# Cornverter.net
KiCad netlist of a schematic drawn in EAGLE
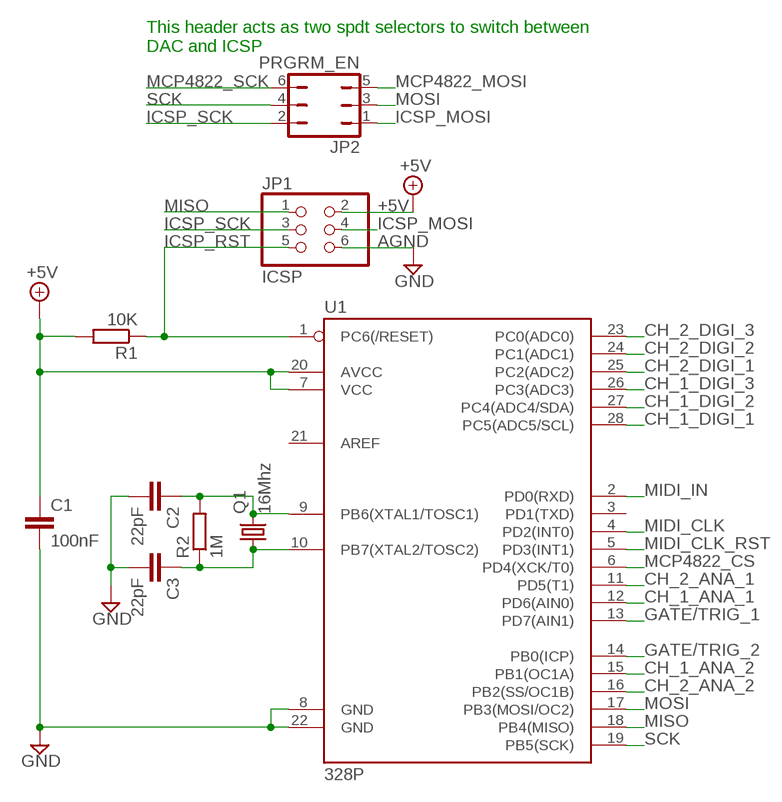
[diagram p0: schematic, sheet 1]
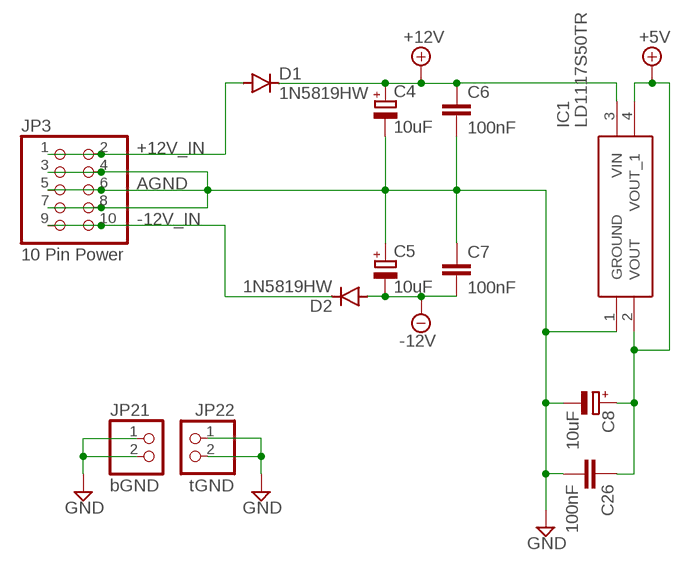
[diagram p1: schematic, sheet 2]
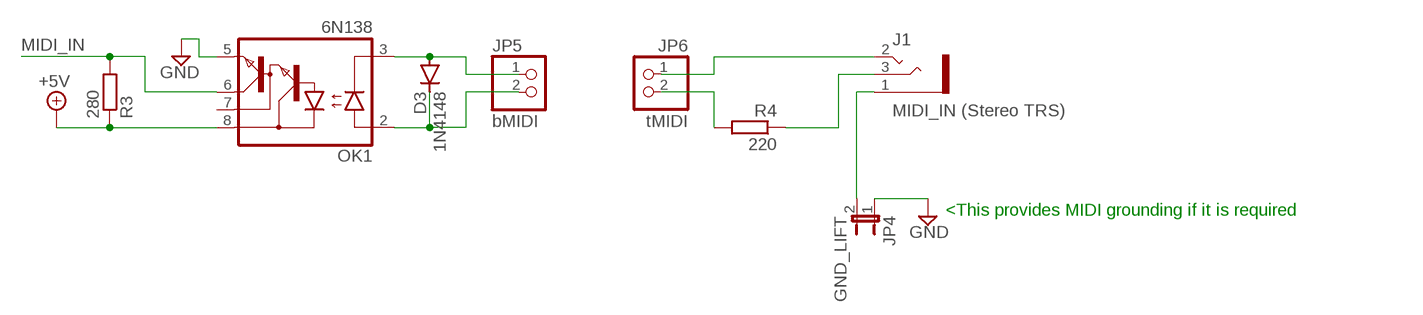
[diagram p2: schematic, sheet 3]
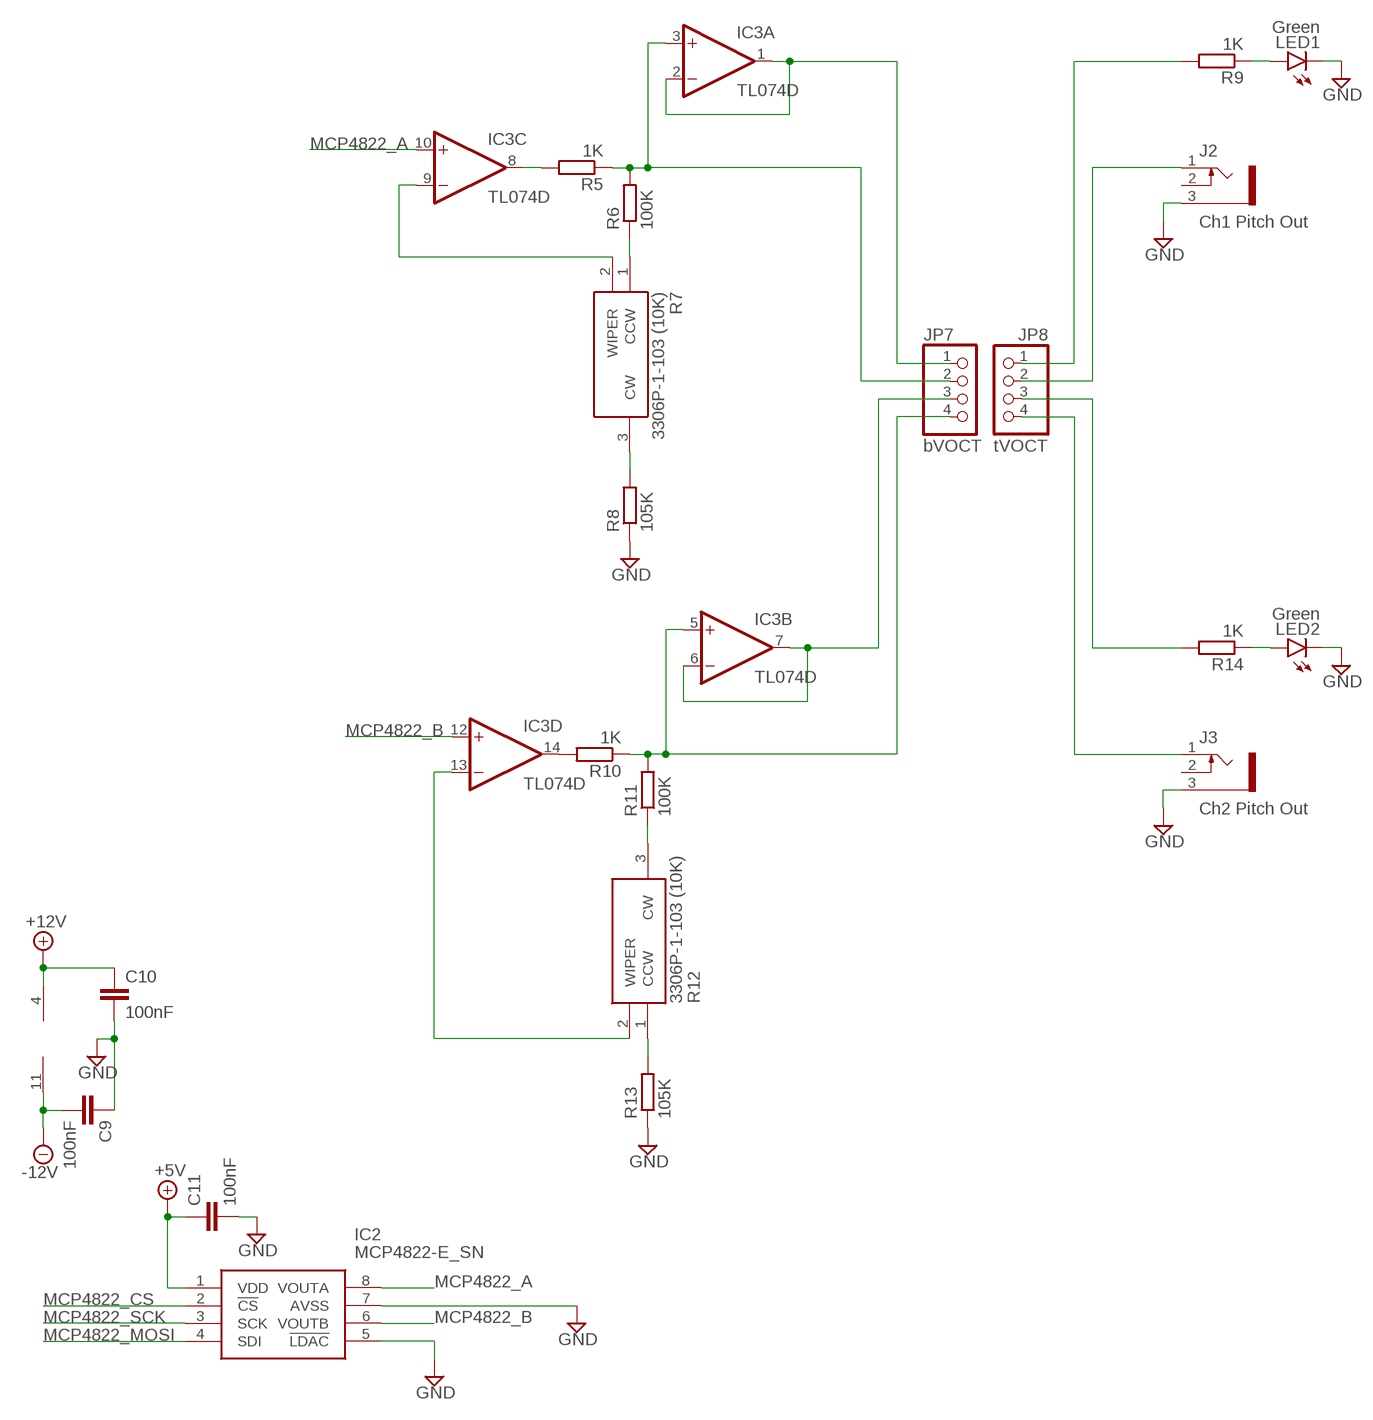
[diagram p3: schematic, sheet 4]
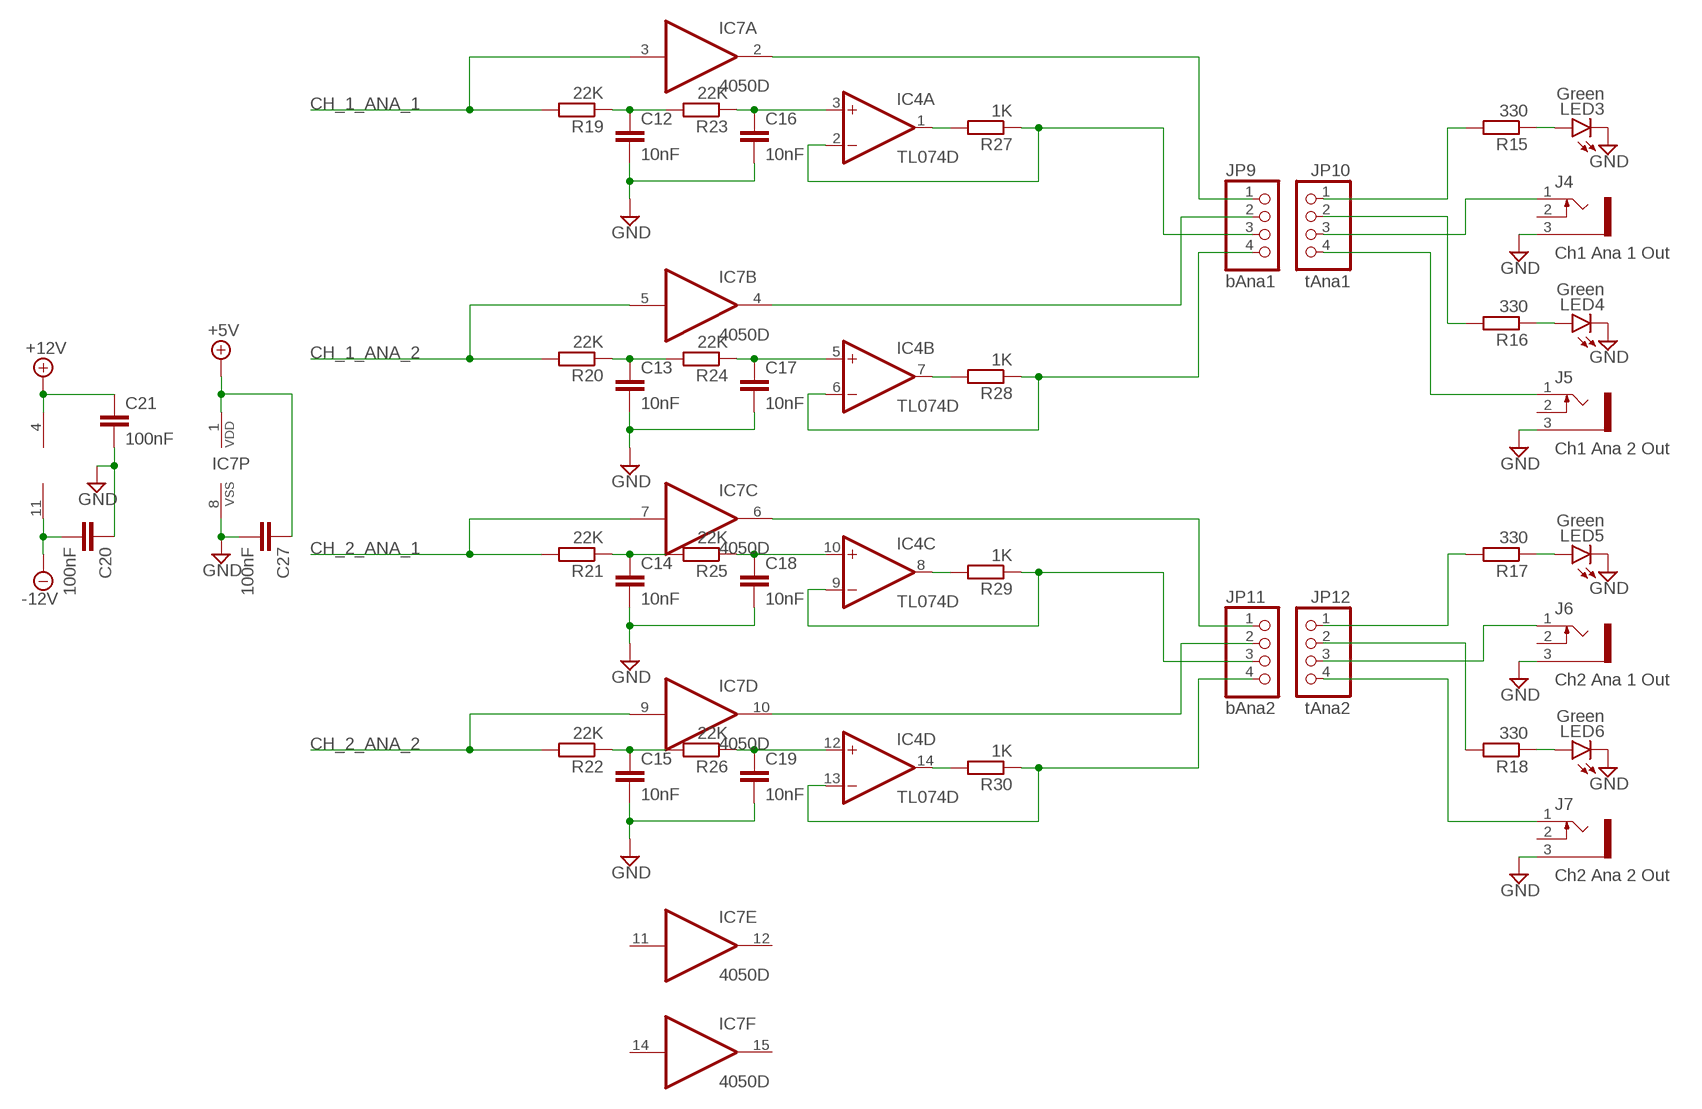
[diagram p4: schematic, sheet 5]
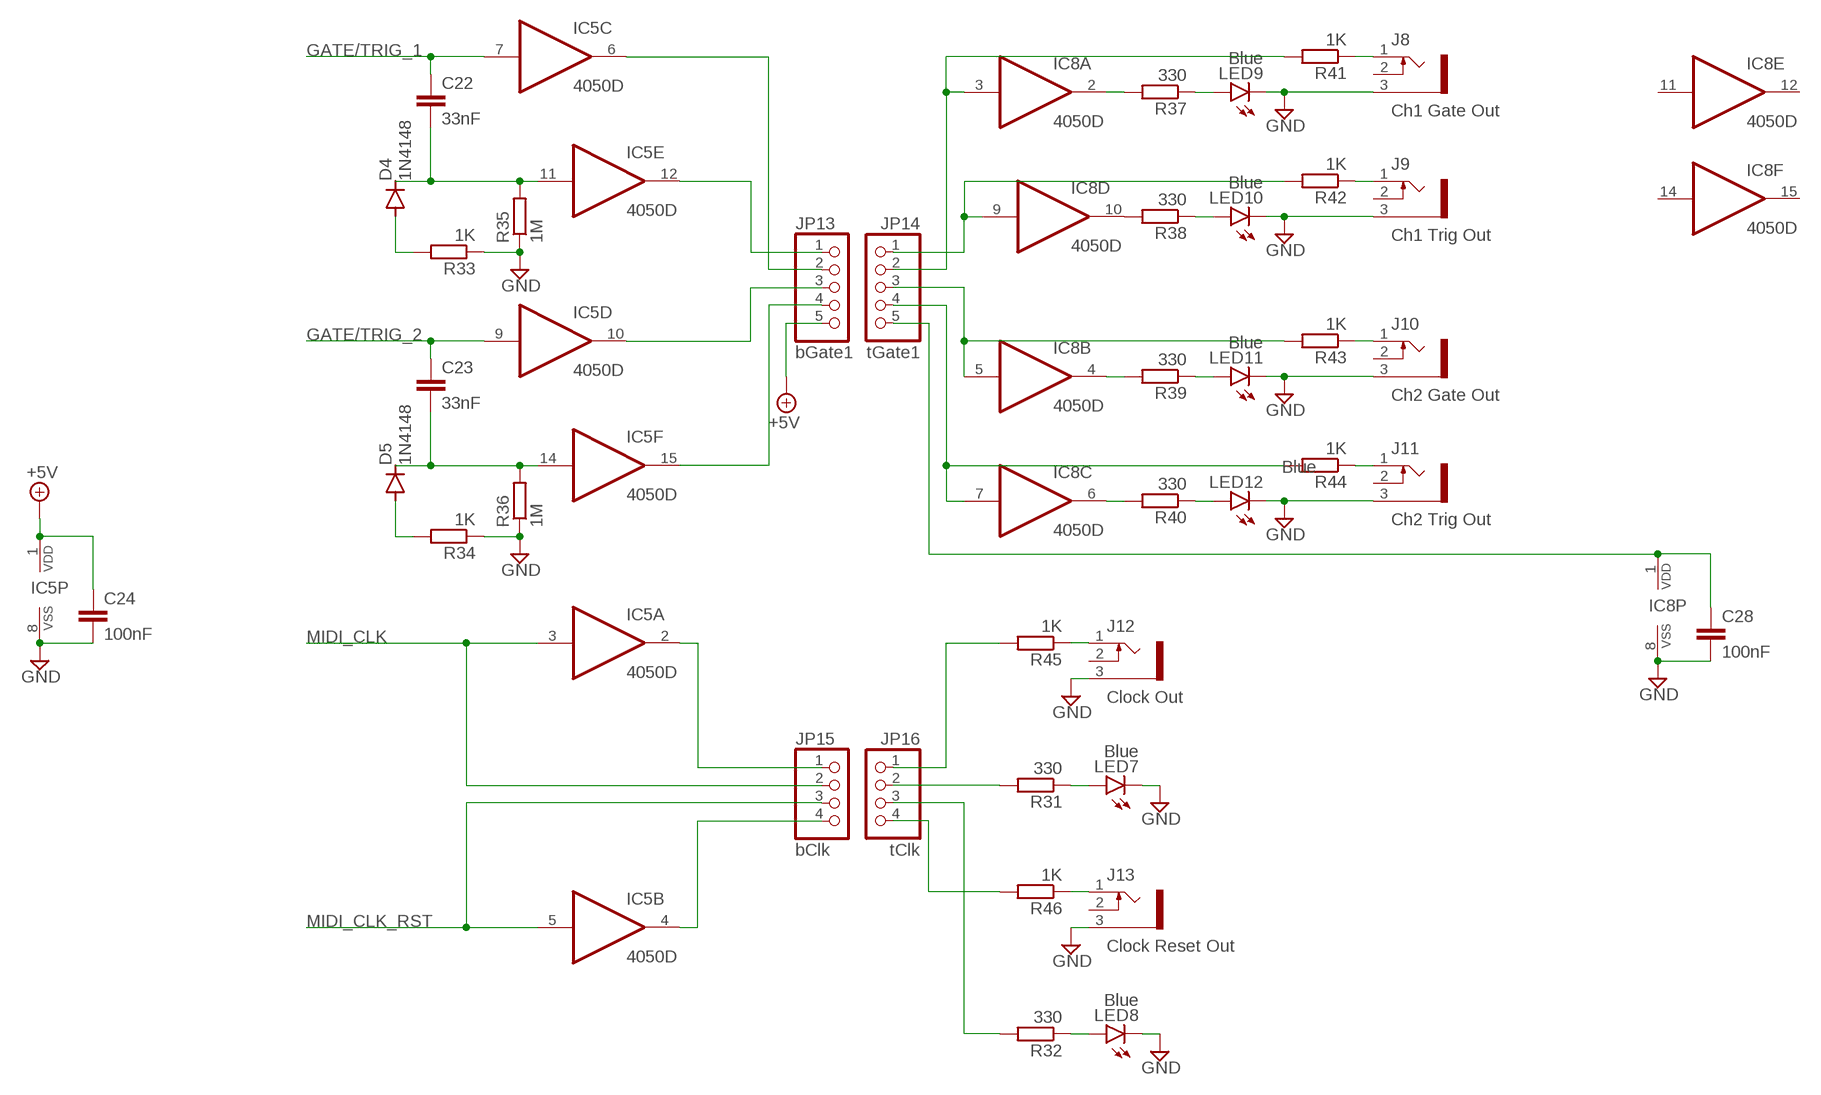
[diagram p5: schematic, sheet 6]
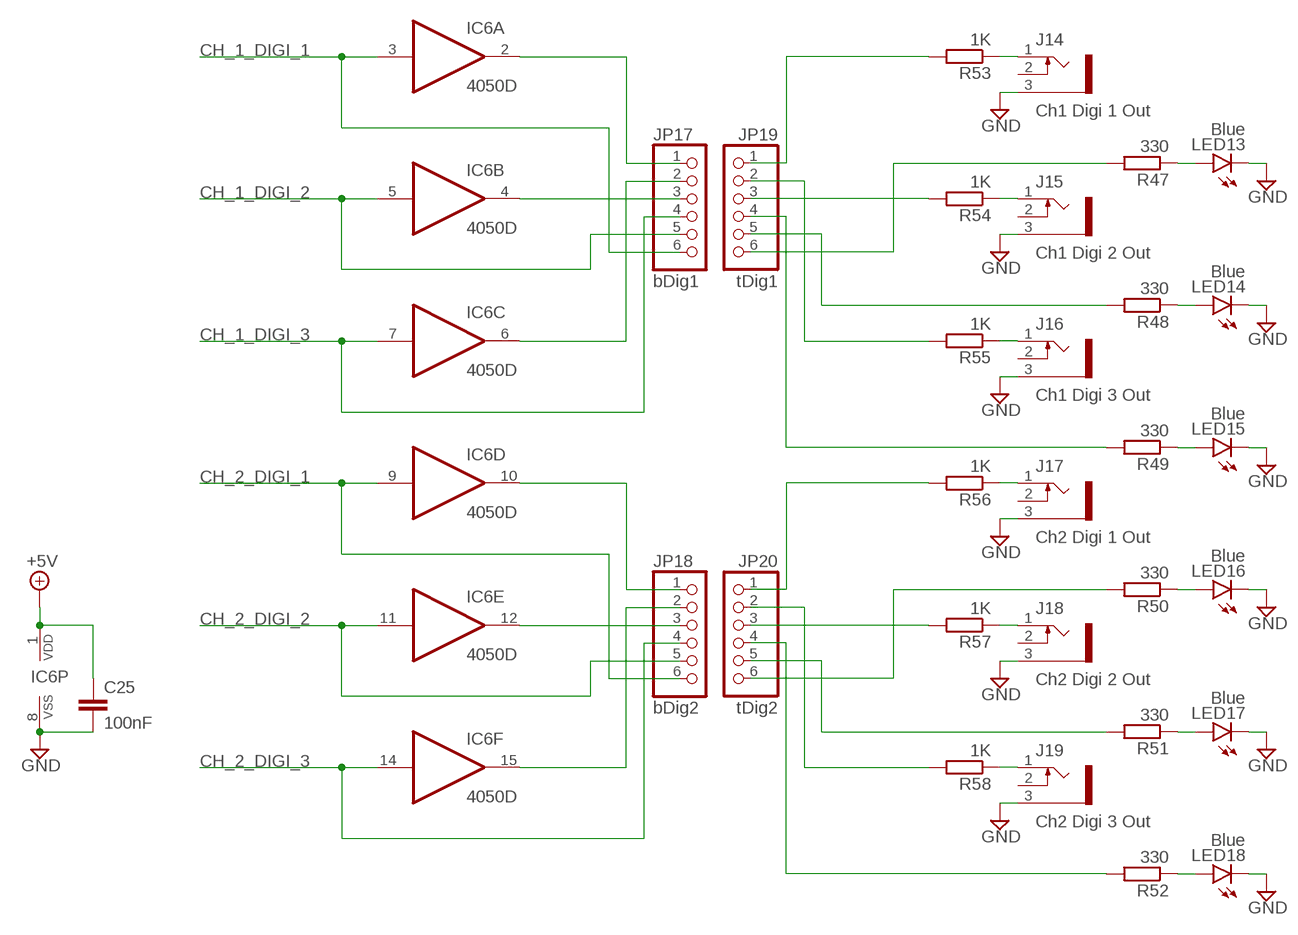
[diagram p6: schematic, sheet 7]

(export (version "E")
  (design (tool "Eeschema 10.0.6"))
  (components
    (comp (ref "C1")
      (value "100nF")
      (footprint "eagle-import:C1206")
      (libsource (lib "eagle-import") (part "C-EUC1206"))
    )
    (comp (ref "C2")
      (value "22pF")
      (footprint "eagle-import:C1206")
      (libsource (lib "eagle-import") (part "C-EUC1206"))
    )
    (comp (ref "C3")
      (value "22pF")
      (footprint "eagle-import:C1206")
      (libsource (lib "eagle-import") (part "C-EUC1206"))
    )
    (comp (ref "JP1")
      (value "ICSP")
      (footprint "eagle-import:2X03")
      (libsource (lib "eagle-import") (part "PINHD-2X3"))
    )
    (comp (ref "JP2")
      (value "PRGRM_EN")
      (footprint "eagle-import:JP3Q")
      (libsource (lib "eagle-import") (part "JP3Q"))
    )
    (comp (ref "Q1")
      (value "16Mhz")
      (footprint "eagle-import:HC49_S")
      (libsource (lib "eagle-import") (part "CRYSTALHC49S"))
    )
    (comp (ref "R1")
      (value "10K")
      (footprint "eagle-import:R1206")
      (libsource (lib "eagle-import") (part "resistor_348_R-EU_R1206"))
    )
    (comp (ref "R2")
      (value "1M")
      (footprint "eagle-import:R1206")
      (libsource (lib "eagle-import") (part "R-EU_R1206"))
    )
    (comp (ref "U1")
      (value "328P")
      (footprint "eagle-import:DIP28")
      (libsource (lib "eagle-import") (part "ATMEGA328P_PDIP"))
    )
    (comp (ref "C22")
      (value "33nF")
      (footprint "eagle-import:C1206")
      (libsource (lib "eagle-import") (part "C-EUC1206"))
    )
    (comp (ref "C23")
      (value "33nF")
      (footprint "eagle-import:C1206")
      (libsource (lib "eagle-import") (part "C-EUC1206"))
    )
    (comp (ref "C24")
      (value "100nF")
      (footprint "eagle-import:C1206")
      (libsource (lib "eagle-import") (part "C-EUC1206"))
    )
    (comp (ref "C28")
      (value "100nF")
      (footprint "eagle-import:C1206")
      (libsource (lib "eagle-import") (part "C-EUC1206"))
    )
    (comp (ref "D4")
      (value "1N4148")
      (footprint "eagle-import:DO35-7")
      (libsource (lib "eagle-import") (part "1N4148DO35-7"))
    )
    (comp (ref "D5")
      (value "1N4148")
      (footprint "eagle-import:DO35-7")
      (libsource (lib "eagle-import") (part "1N4148DO35-7"))
    )
    (comp (ref "IC5")
      (value "4050D")
      (footprint "eagle-import:SO16")
      (libsource (lib "eagle-import") (part "4050D"))
    )
    (comp (ref "IC8")
      (value "4050D")
      (footprint "eagle-import:SO16")
      (libsource (lib "eagle-import") (part "4050D"))
    )
    (comp (ref "J8")
      (value "Ch1 Gate Out")
      (footprint "eagle-import:WQP-PJ301M-12_JACK")
      (libsource (lib "eagle-import") (part "WQP-PJ301M-12_JACK"))
    )
    (comp (ref "J9")
      (value "Ch1 Trig Out")
      (footprint "eagle-import:WQP-PJ301M-12_JACK")
      (libsource (lib "eagle-import") (part "WQP-PJ301M-12_JACK"))
    )
    (comp (ref "J10")
      (value "Ch2 Gate Out")
      (footprint "eagle-import:WQP-PJ301M-12_JACK")
      (libsource (lib "eagle-import") (part "WQP-PJ301M-12_JACK"))
    )
    (comp (ref "J11")
      (value "Ch2 Trig Out")
      (footprint "eagle-import:WQP-PJ301M-12_JACK")
      (libsource (lib "eagle-import") (part "WQP-PJ301M-12_JACK"))
    )
    (comp (ref "J12")
      (value "Clock Out")
      (footprint "eagle-import:WQP-PJ301M-12_JACK")
      (libsource (lib "eagle-import") (part "WQP-PJ301M-12_JACK"))
    )
    (comp (ref "J13")
      (value "Clock Reset Out")
      (footprint "eagle-import:WQP-PJ301M-12_JACK")
      (libsource (lib "eagle-import") (part "WQP-PJ301M-12_JACK"))
    )
    (comp (ref "JP13")
      (value "bGate1")
      (footprint "eagle-import:1X05")
      (libsource (lib "eagle-import") (part "PINHD-1X5"))
    )
    (comp (ref "JP14")
      (value "tGate1")
      (footprint "eagle-import:1X05")
      (libsource (lib "eagle-import") (part "PINHD-1X5"))
    )
    (comp (ref "JP15")
      (value "bClk")
      (footprint "eagle-import:1X04")
      (libsource (lib "eagle-import") (part "PINHD-1X4"))
    )
    (comp (ref "JP16")
      (value "tClk")
      (footprint "eagle-import:1X04")
      (libsource (lib "eagle-import") (part "PINHD-1X4"))
    )
    (comp (ref "LED7")
      (value "Blue")
      (footprint "eagle-import:LED3MM")
      (libsource (lib "eagle-import") (part "LED3MM"))
    )
    (comp (ref "LED8")
      (value "Blue")
      (footprint "eagle-import:LED3MM")
      (libsource (lib "eagle-import") (part "LED3MM"))
    )
    (comp (ref "LED9")
      (value "Blue")
      (footprint "eagle-import:LED3MM")
      (libsource (lib "eagle-import") (part "LED3MM"))
    )
    (comp (ref "LED10")
      (value "Blue")
      (footprint "eagle-import:LED3MM")
      (libsource (lib "eagle-import") (part "LED3MM"))
    )
    (comp (ref "LED11")
      (value "Blue")
      (footprint "eagle-import:LED3MM")
      (libsource (lib "eagle-import") (part "LED3MM"))
    )
    (comp (ref "LED12")
      (value "Blue")
      (footprint "eagle-import:LED3MM")
      (libsource (lib "eagle-import") (part "LED3MM"))
    )
    (comp (ref "R31")
      (value "330")
      (footprint "eagle-import:R1206")
      (libsource (lib "eagle-import") (part "R-EU_R1206"))
    )
    (comp (ref "R32")
      (value "330")
      (footprint "eagle-import:R1206")
      (libsource (lib "eagle-import") (part "R-EU_R1206"))
    )
    (comp (ref "R33")
      (value "1K")
      (footprint "eagle-import:R1206")
      (libsource (lib "eagle-import") (part "R-EU_R1206"))
    )
    (comp (ref "R34")
      (value "1K")
      (footprint "eagle-import:R1206")
      (libsource (lib "eagle-import") (part "R-EU_R1206"))
    )
    (comp (ref "R35")
      (value "1M")
      (footprint "eagle-import:R1206")
      (libsource (lib "eagle-import") (part "R-EU_R1206"))
    )
    (comp (ref "R36")
      (value "1M")
      (footprint "eagle-import:R1206")
      (libsource (lib "eagle-import") (part "R-EU_R1206"))
    )
    (comp (ref "R37")
      (value "330")
      (footprint "eagle-import:R1206")
      (libsource (lib "eagle-import") (part "R-EU_R1206"))
    )
    (comp (ref "R38")
      (value "330")
      (footprint "eagle-import:R1206")
      (libsource (lib "eagle-import") (part "R-EU_R1206"))
    )
    (comp (ref "R39")
      (value "330")
      (footprint "eagle-import:R1206")
      (libsource (lib "eagle-import") (part "R-EU_R1206"))
    )
    (comp (ref "R40")
      (value "330")
      (footprint "eagle-import:R1206")
      (libsource (lib "eagle-import") (part "R-EU_R1206"))
    )
    (comp (ref "R41")
      (value "1K")
      (footprint "eagle-import:R1206")
      (libsource (lib "eagle-import") (part "R-EU_R1206"))
    )
    (comp (ref "R42")
      (value "1K")
      (footprint "eagle-import:R1206")
      (libsource (lib "eagle-import") (part "R-EU_R1206"))
    )
    (comp (ref "R43")
      (value "1K")
      (footprint "eagle-import:R1206")
      (libsource (lib "eagle-import") (part "R-EU_R1206"))
    )
    (comp (ref "R44")
      (value "1K")
      (footprint "eagle-import:R1206")
      (libsource (lib "eagle-import") (part "R-EU_R1206"))
    )
    (comp (ref "R45")
      (value "1K")
      (footprint "eagle-import:R1206")
      (libsource (lib "eagle-import") (part "R-EU_R1206"))
    )
    (comp (ref "R46")
      (value "1K")
      (footprint "eagle-import:R1206")
      (libsource (lib "eagle-import") (part "R-EU_R1206"))
    )
    (comp (ref "C9")
      (value "100nF")
      (footprint "eagle-import:C1206")
      (libsource (lib "eagle-import") (part "C-EUC1206"))
    )
    (comp (ref "C10")
      (value "100nF")
      (footprint "eagle-import:C1206")
      (libsource (lib "eagle-import") (part "C-EUC1206"))
    )
    (comp (ref "C11")
      (value "100nF")
      (footprint "eagle-import:C1206")
      (libsource (lib "eagle-import") (part "C-EUC1206"))
    )
    (comp (ref "IC2")
      (value "MCP4822-E_SN")
      (footprint "eagle-import:SOIC127P600X175-8N")
      (fields
        (field (name "MANUFACTURER_PART_NUMBER") "MCP4822-E/SN")
        (field (name "MOUSER_PART_NUMBER") "579-MCP4822-E/SN")
      )
      (libsource (lib "eagle-import") (part "MCP4822-E_SN"))
    )
    (comp (ref "IC3")
      (value "TL074D")
      (footprint "eagle-import:SO14")
      (libsource (lib "eagle-import") (part "TL074D"))
    )
    (comp (ref "J2")
      (value "Ch1 Pitch Out")
      (footprint "eagle-import:WQP-PJ301M-12_JACK")
      (libsource (lib "eagle-import") (part "WQP-PJ301M-12_JACK"))
    )
    (comp (ref "J3")
      (value "Ch2 Pitch Out")
      (footprint "eagle-import:WQP-PJ301M-12_JACK")
      (libsource (lib "eagle-import") (part "WQP-PJ301M-12_JACK"))
    )
    (comp (ref "JP7")
      (value "bVOCT")
      (footprint "eagle-import:1X04")
      (libsource (lib "eagle-import") (part "PINHD-1X4"))
    )
    (comp (ref "JP8")
      (value "tVOCT")
      (footprint "eagle-import:1X04")
      (libsource (lib "eagle-import") (part "PINHD-1X4"))
    )
    (comp (ref "LED1")
      (value "Green")
      (footprint "eagle-import:LED3MM")
      (libsource (lib "eagle-import") (part "LED3MM"))
    )
    (comp (ref "LED2")
      (value "Green")
      (footprint "eagle-import:LED3MM")
      (libsource (lib "eagle-import") (part "LED3MM"))
    )
    (comp (ref "R5")
      (value "1K")
      (footprint "eagle-import:R1206")
      (libsource (lib "eagle-import") (part "R-EU_R1206"))
    )
    (comp (ref "R6")
      (value "100K")
      (footprint "eagle-import:R1206")
      (libsource (lib "eagle-import") (part "R-EU_R1206"))
    )
    (comp (ref "R7")
      (value "3306P-1-103 (10K)")
      (footprint "eagle-import:3306P1103")
      (fields
        (field (name "MANUFACTURER_PART_NUMBER") "3306P-1-103")
        (field (name "MOUSER_PART_NUMBER") "652-3306P-1-103")
      )
      (libsource (lib "eagle-import") (part "3306P-1-103"))
    )
    (comp (ref "R8")
      (value "105K")
      (footprint "eagle-import:R1206")
      (libsource (lib "eagle-import") (part "R-EU_R1206"))
    )
    (comp (ref "R9")
      (value "1K")
      (footprint "eagle-import:R1206")
      (libsource (lib "eagle-import") (part "R-EU_R1206"))
    )
    (comp (ref "R10")
      (value "1K")
      (footprint "eagle-import:R1206")
      (libsource (lib "eagle-import") (part "R-EU_R1206"))
    )
    (comp (ref "R11")
      (value "100K")
      (footprint "eagle-import:R1206")
      (libsource (lib "eagle-import") (part "R-EU_R1206"))
    )
    (comp (ref "R12")
      (value "3306P-1-103 (10K)")
      (footprint "eagle-import:3306P1103")
      (fields
        (field (name "MANUFACTURER_PART_NUMBER") "3306P-1-103")
        (field (name "MOUSER_PART_NUMBER") "652-3306P-1-103")
      )
      (libsource (lib "eagle-import") (part "3306P-1-103"))
    )
    (comp (ref "R13")
      (value "105K")
      (footprint "eagle-import:R1206")
      (libsource (lib "eagle-import") (part "R-EU_R1206"))
    )
    (comp (ref "R14")
      (value "1K")
      (footprint "eagle-import:R1206")
      (libsource (lib "eagle-import") (part "R-EU_R1206"))
    )
    (comp (ref "C25")
      (value "100nF")
      (footprint "eagle-import:C1206")
      (libsource (lib "eagle-import") (part "C-EUC1206"))
    )
    (comp (ref "IC6")
      (value "4050D")
      (footprint "eagle-import:SO16")
      (libsource (lib "eagle-import") (part "4050D"))
    )
    (comp (ref "J14")
      (value "Ch1 Digi 1 Out")
      (footprint "eagle-import:WQP-PJ301M-12_JACK")
      (libsource (lib "eagle-import") (part "WQP-PJ301M-12_JACK"))
    )
    (comp (ref "J15")
      (value "Ch1 Digi 2 Out")
      (footprint "eagle-import:WQP-PJ301M-12_JACK")
      (libsource (lib "eagle-import") (part "WQP-PJ301M-12_JACK"))
    )
    (comp (ref "J16")
      (value "Ch1 Digi 3 Out")
      (footprint "eagle-import:WQP-PJ301M-12_JACK")
      (libsource (lib "eagle-import") (part "WQP-PJ301M-12_JACK"))
    )
    (comp (ref "J17")
      (value "Ch2 Digi 1 Out")
      (footprint "eagle-import:WQP-PJ301M-12_JACK")
      (libsource (lib "eagle-import") (part "WQP-PJ301M-12_JACK"))
    )
    (comp (ref "J18")
      (value "Ch2 Digi 2 Out")
      (footprint "eagle-import:WQP-PJ301M-12_JACK")
      (libsource (lib "eagle-import") (part "WQP-PJ301M-12_JACK"))
    )
    (comp (ref "J19")
      (value "Ch2 Digi 3 Out")
      (footprint "eagle-import:WQP-PJ301M-12_JACK")
      (libsource (lib "eagle-import") (part "WQP-PJ301M-12_JACK"))
    )
    (comp (ref "JP17")
      (value "bDig1")
      (footprint "eagle-import:1X06")
      (libsource (lib "eagle-import") (part "PINHD-1X6"))
    )
    (comp (ref "JP18")
      (value "bDig2")
      (footprint "eagle-import:1X06")
      (libsource (lib "eagle-import") (part "PINHD-1X6"))
    )
    (comp (ref "JP19")
      (value "tDig1")
      (footprint "eagle-import:1X06")
      (libsource (lib "eagle-import") (part "PINHD-1X6"))
    )
    (comp (ref "JP20")
      (value "tDig2")
      (footprint "eagle-import:1X06")
      (libsource (lib "eagle-import") (part "PINHD-1X6"))
    )
    (comp (ref "LED13")
      (value "Blue")
      (footprint "eagle-import:LED3MM")
      (libsource (lib "eagle-import") (part "LED3MM"))
    )
    (comp (ref "LED14")
      (value "Blue")
      (footprint "eagle-import:LED3MM")
      (libsource (lib "eagle-import") (part "LED3MM"))
    )
    (comp (ref "LED15")
      (value "Blue")
      (footprint "eagle-import:LED3MM")
      (libsource (lib "eagle-import") (part "LED3MM"))
    )
    (comp (ref "LED16")
      (value "Blue")
      (footprint "eagle-import:LED3MM")
      (libsource (lib "eagle-import") (part "LED3MM"))
    )
    (comp (ref "LED17")
      (value "Blue")
      (footprint "eagle-import:LED3MM")
      (libsource (lib "eagle-import") (part "LED3MM"))
    )
    (comp (ref "LED18")
      (value "Blue")
      (footprint "eagle-import:LED3MM")
      (libsource (lib "eagle-import") (part "LED3MM"))
    )
    (comp (ref "R47")
      (value "330")
      (footprint "eagle-import:R1206")
      (libsource (lib "eagle-import") (part "R-EU_R1206"))
    )
    (comp (ref "R48")
      (value "330")
      (footprint "eagle-import:R1206")
      (libsource (lib "eagle-import") (part "R-EU_R1206"))
    )
    (comp (ref "R49")
      (value "330")
      (footprint "eagle-import:R1206")
      (libsource (lib "eagle-import") (part "R-EU_R1206"))
    )
    (comp (ref "R50")
      (value "330")
      (footprint "eagle-import:R1206")
      (libsource (lib "eagle-import") (part "R-EU_R1206"))
    )
    (comp (ref "R51")
      (value "330")
      (footprint "eagle-import:R1206")
      (libsource (lib "eagle-import") (part "R-EU_R1206"))
    )
    (comp (ref "R52")
      (value "330")
      (footprint "eagle-import:R1206")
      (libsource (lib "eagle-import") (part "R-EU_R1206"))
    )
    (comp (ref "R53")
      (value "1K")
      (footprint "eagle-import:R1206")
      (libsource (lib "eagle-import") (part "R-EU_R1206"))
    )
    (comp (ref "R54")
      (value "1K")
      (footprint "eagle-import:R1206")
      (libsource (lib "eagle-import") (part "R-EU_R1206"))
    )
    (comp (ref "R55")
      (value "1K")
      (footprint "eagle-import:R1206")
      (libsource (lib "eagle-import") (part "R-EU_R1206"))
    )
    (comp (ref "R56")
      (value "1K")
      (footprint "eagle-import:R1206")
      (libsource (lib "eagle-import") (part "R-EU_R1206"))
    )
    (comp (ref "R57")
      (value "1K")
      (footprint "eagle-import:R1206")
      (libsource (lib "eagle-import") (part "R-EU_R1206"))
    )
    (comp (ref "R58")
      (value "1K")
      (footprint "eagle-import:R1206")
      (libsource (lib "eagle-import") (part "R-EU_R1206"))
    )
    (comp (ref "D3")
      (value "1N4148")
      (footprint "eagle-import:DO35-7")
      (libsource (lib "eagle-import") (part "1N4148DO35-7"))
    )
    (comp (ref "J1")
      (value "MIDI_IN (Stereo TRS)")
      (footprint "eagle-import:WQP-PJ301M-12-ST_JACK")
      (libsource (lib "eagle-import") (part "WQP-PJ301M-12-ST_JACK"))
    )
    (comp (ref "JP4")
      (value "GND_LIFT")
      (footprint "eagle-import:JP1")
      (libsource (lib "eagle-import") (part "JP1E"))
    )
    (comp (ref "JP5")
      (value "bMIDI")
      (footprint "eagle-import:1X02")
      (libsource (lib "eagle-import") (part "PINHD-1X2"))
    )
    (comp (ref "JP6")
      (value "tMIDI")
      (footprint "eagle-import:1X02")
      (libsource (lib "eagle-import") (part "PINHD-1X2"))
    )
    (comp (ref "OK1")
      (value "6N138")
      (footprint "eagle-import:DIL08")
      (fields (field (name "MF") "VISHAY/TELEFUNKEN") (field (name "SPICEPREFIX") "X"))
      (libsource (lib "eagle-import") (part "6N138"))
    )
    (comp (ref "R3")
      (value "280")
      (footprint "eagle-import:R1206")
      (libsource (lib "eagle-import") (part "R-EU_R1206"))
    )
    (comp (ref "R4")
      (value "220")
      (footprint "eagle-import:R1206")
      (libsource (lib "eagle-import") (part "R-EU_R1206"))
    )
    (comp (ref "C12")
      (value "10nF")
      (footprint "eagle-import:C1206")
      (libsource (lib "eagle-import") (part "C-EUC1206"))
    )
    (comp (ref "C13")
      (value "10nF")
      (footprint "eagle-import:C1206")
      (libsource (lib "eagle-import") (part "C-EUC1206"))
    )
    (comp (ref "C14")
      (value "10nF")
      (footprint "eagle-import:C1206")
      (libsource (lib "eagle-import") (part "C-EUC1206"))
    )
    (comp (ref "C15")
      (value "10nF")
      (footprint "eagle-import:C1206")
      (libsource (lib "eagle-import") (part "C-EUC1206"))
    )
    (comp (ref "C16")
      (value "10nF")
      (footprint "eagle-import:C1206")
      (libsource (lib "eagle-import") (part "C-EUC1206"))
    )
    (comp (ref "C17")
      (value "10nF")
      (footprint "eagle-import:C1206")
      (libsource (lib "eagle-import") (part "C-EUC1206"))
    )
    (comp (ref "C18")
      (value "10nF")
      (footprint "eagle-import:C1206")
      (libsource (lib "eagle-import") (part "C-EUC1206"))
    )
    (comp (ref "C19")
      (value "10nF")
      (footprint "eagle-import:C1206")
      (libsource (lib "eagle-import") (part "C-EUC1206"))
    )
    (comp (ref "C20")
      (value "100nF")
      (footprint "eagle-import:C1206")
      (libsource (lib "eagle-import") (part "C-EUC1206"))
    )
    (comp (ref "C21")
      (value "100nF")
      (footprint "eagle-import:C1206")
      (libsource (lib "eagle-import") (part "C-EUC1206"))
    )
    (comp (ref "C27")
      (value "100nF")
      (footprint "eagle-import:C1206")
      (libsource (lib "eagle-import") (part "C-EUC1206"))
    )
    (comp (ref "IC4")
      (value "TL074D")
      (footprint "eagle-import:SO14")
      (libsource (lib "eagle-import") (part "TL074D"))
    )
    (comp (ref "IC7")
      (value "4050D")
      (footprint "eagle-import:SO16")
      (libsource (lib "eagle-import") (part "4050D"))
    )
    (comp (ref "J4")
      (value "Ch1 Ana 1 Out")
      (footprint "eagle-import:WQP-PJ301M-12_JACK")
      (libsource (lib "eagle-import") (part "WQP-PJ301M-12_JACK"))
    )
    (comp (ref "J5")
      (value "Ch1 Ana 2 Out")
      (footprint "eagle-import:WQP-PJ301M-12_JACK")
      (libsource (lib "eagle-import") (part "WQP-PJ301M-12_JACK"))
    )
    (comp (ref "J6")
      (value "Ch2 Ana 1 Out")
      (footprint "eagle-import:WQP-PJ301M-12_JACK")
      (libsource (lib "eagle-import") (part "WQP-PJ301M-12_JACK"))
    )
    (comp (ref "J7")
      (value "Ch2 Ana 2 Out")
      (footprint "eagle-import:WQP-PJ301M-12_JACK")
      (libsource (lib "eagle-import") (part "WQP-PJ301M-12_JACK"))
    )
    (comp (ref "JP9")
      (value "bAna1")
      (footprint "eagle-import:1X04")
      (libsource (lib "eagle-import") (part "PINHD-1X4"))
    )
    (comp (ref "JP10")
      (value "tAna1")
      (footprint "eagle-import:1X04")
      (libsource (lib "eagle-import") (part "PINHD-1X4"))
    )
    (comp (ref "JP11")
      (value "bAna2")
      (footprint "eagle-import:1X04")
      (libsource (lib "eagle-import") (part "PINHD-1X4"))
    )
    (comp (ref "JP12")
      (value "tAna2")
      (footprint "eagle-import:1X04")
      (libsource (lib "eagle-import") (part "PINHD-1X4"))
    )
    (comp (ref "LED3")
      (value "Green")
      (footprint "eagle-import:LED3MM")
      (libsource (lib "eagle-import") (part "LED3MM"))
    )
    (comp (ref "LED4")
      (value "Green")
      (footprint "eagle-import:LED3MM")
      (libsource (lib "eagle-import") (part "LED3MM"))
    )
    (comp (ref "LED5")
      (value "Green")
      (footprint "eagle-import:LED3MM")
      (libsource (lib "eagle-import") (part "LED3MM"))
    )
    (comp (ref "LED6")
      (value "Green")
      (footprint "eagle-import:LED3MM")
      (libsource (lib "eagle-import") (part "LED3MM"))
    )
    (comp (ref "R15")
      (value "330")
      (footprint "eagle-import:R1206")
      (libsource (lib "eagle-import") (part "R-EU_R1206"))
    )
    (comp (ref "R16")
      (value "330")
      (footprint "eagle-import:R1206")
      (libsource (lib "eagle-import") (part "R-EU_R1206"))
    )
    (comp (ref "R17")
      (value "330")
      (footprint "eagle-import:R1206")
      (libsource (lib "eagle-import") (part "R-EU_R1206"))
    )
    (comp (ref "R18")
      (value "330")
      (footprint "eagle-import:R1206")
      (libsource (lib "eagle-import") (part "R-EU_R1206"))
    )
    (comp (ref "R19")
      (value "22K")
      (footprint "eagle-import:R1206")
      (libsource (lib "eagle-import") (part "R-EU_R1206"))
    )
    (comp (ref "R20")
      (value "22K")
      (footprint "eagle-import:R1206")
      (libsource (lib "eagle-import") (part "R-EU_R1206"))
    )
    (comp (ref "R21")
      (value "22K")
      (footprint "eagle-import:R1206")
      (libsource (lib "eagle-import") (part "R-EU_R1206"))
    )
    (comp (ref "R22")
      (value "22K")
      (footprint "eagle-import:R1206")
      (libsource (lib "eagle-import") (part "R-EU_R1206"))
    )
    (comp (ref "R23")
      (value "22K")
      (footprint "eagle-import:R1206")
      (libsource (lib "eagle-import") (part "R-EU_R1206"))
    )
    (comp (ref "R24")
      (value "22K")
      (footprint "eagle-import:R1206")
      (libsource (lib "eagle-import") (part "R-EU_R1206"))
    )
    (comp (ref "R25")
      (value "22K")
      (footprint "eagle-import:R1206")
      (libsource (lib "eagle-import") (part "R-EU_R1206"))
    )
    (comp (ref "R26")
      (value "22K")
      (footprint "eagle-import:R1206")
      (libsource (lib "eagle-import") (part "R-EU_R1206"))
    )
    (comp (ref "R27")
      (value "1K")
      (footprint "eagle-import:R1206")
      (libsource (lib "eagle-import") (part "R-EU_R1206"))
    )
    (comp (ref "R28")
      (value "1K")
      (footprint "eagle-import:R1206")
      (libsource (lib "eagle-import") (part "R-EU_R1206"))
    )
    (comp (ref "R29")
      (value "1K")
      (footprint "eagle-import:R1206")
      (libsource (lib "eagle-import") (part "R-EU_R1206"))
    )
    (comp (ref "R30")
      (value "1K")
      (footprint "eagle-import:R1206")
      (libsource (lib "eagle-import") (part "R-EU_R1206"))
    )
    (comp (ref "C4")
      (value "10uF")
      (footprint "eagle-import:E2-5")
      (libsource (lib "eagle-import") (part "CPOL-EUE2-5"))
    )
    (comp (ref "C5")
      (value "10uF")
      (footprint "eagle-import:E2-5")
      (libsource (lib "eagle-import") (part "CPOL-EUE2-5"))
    )
    (comp (ref "C6")
      (value "100nF")
      (footprint "eagle-import:C1206")
      (libsource (lib "eagle-import") (part "C-EUC1206"))
    )
    (comp (ref "C7")
      (value "100nF")
      (footprint "eagle-import:C1206")
      (libsource (lib "eagle-import") (part "C-EUC1206"))
    )
    (comp (ref "C8")
      (value "10uF")
      (footprint "eagle-import:E2-5")
      (libsource (lib "eagle-import") (part "CPOL-EUE2-5"))
    )
    (comp (ref "C26")
      (value "100nF")
      (footprint "eagle-import:C1206")
      (libsource (lib "eagle-import") (part "C-EUC1206"))
    )
    (comp (ref "D1")
      (value "1N5819HW")
      (footprint "eagle-import:SOD123")
      (libsource (lib "eagle-import") (part "DIODE-SOD123"))
    )
    (comp (ref "D2")
      (value "1N5819HW")
      (footprint "eagle-import:SOD123")
      (libsource (lib "eagle-import") (part "DIODE-SOD123"))
    )
    (comp (ref "IC1")
      (value "LD1117S50TR")
      (footprint "eagle-import:SOT230P700X190-4N")
      (fields (field (name "MOUSER_PART_NUMBER") "511-LD1117S50"))
      (libsource (lib "eagle-import") (part "LD1117S50TR"))
    )
    (comp (ref "JP3")
      (value "10 Pin Power")
      (footprint "eagle-import:2X05")
      (libsource (lib "eagle-import") (part "PINHD-2X5"))
    )
    (comp (ref "JP21")
      (value "bGND")
      (footprint "eagle-import:1X02")
      (libsource (lib "eagle-import") (part "PINHD-1X2"))
    )
    (comp (ref "JP22")
      (value "tGND")
      (footprint "eagle-import:1X02")
      (libsource (lib "eagle-import") (part "PINHD-1X2"))
    )
  )
  (nets
    (net (code "1") (name "+5V") (class "Default")
      (node (ref "C1") (pin "1") (pinfunction "1_1") (pintype "passive"))
      (node (ref "C11") (pin "1") (pinfunction "1_1") (pintype "passive"))
      (node (ref "C24") (pin "1") (pinfunction "1_1") (pintype "passive"))
      (node (ref "C25") (pin "1") (pinfunction "1_1") (pintype "passive"))
      (node (ref "C26") (pin "1") (pinfunction "1_1") (pintype "passive"))
      (node (ref "C27") (pin "1") (pinfunction "1_1") (pintype "passive"))
      (node (ref "C8") (pin "+") (pinfunction "+_+") (pintype "passive"))
      (node (ref "IC1") (pin "2") (pinfunction "VOUT_2") (pintype "power_in"))
      (node (ref "IC1") (pin "4") (pinfunction "VOUT_1_4") (pintype "power_in"))
      (node (ref "IC2") (pin "1") (pinfunction "VDD_1") (pintype "power_in"))
      (node (ref "IC5") (pin "1") (pinfunction "VDD_1") (pintype "power_in"))
      (node (ref "IC6") (pin "1") (pinfunction "VDD_1") (pintype "power_in"))
      (node (ref "IC7") (pin "1") (pinfunction "VDD_1") (pintype "power_in"))
      (node (ref "JP1") (pin "2") (pinfunction "2_2") (pintype "passive"))
      (node (ref "JP13") (pin "5") (pinfunction "5_5") (pintype "passive"))
      (node (ref "OK1") (pin "8") (pinfunction "VCC_8") (pintype "passive"))
      (node (ref "R1") (pin "2") (pinfunction "2_2") (pintype "passive"))
      (node (ref "R3") (pin "1") (pinfunction "1_1") (pintype "passive"))
      (node (ref "U1") (pin "20") (pinfunction "AVCC_20") (pintype "bidirectional"))
      (node (ref "U1") (pin "7") (pinfunction "VCC_7") (pintype "bidirectional"))
    )
    (net (code "2") (name "+12V") (class "Default")
      (node (ref "C10") (pin "1") (pinfunction "1_1") (pintype "passive"))
      (node (ref "C21") (pin "1") (pinfunction "1_1") (pintype "passive"))
      (node (ref "C4") (pin "+") (pinfunction "+_+") (pintype "passive"))
      (node (ref "C6") (pin "1") (pinfunction "1_1") (pintype "passive"))
      (node (ref "D1") (pin "C") (pinfunction "C_C") (pintype "passive"))
      (node (ref "IC1") (pin "3") (pinfunction "VIN_3") (pintype "input"))
      (node (ref "IC3") (pin "4") (pinfunction "V+_4") (pintype "power_in"))
      (node (ref "IC4") (pin "4") (pinfunction "V+_4") (pintype "power_in"))
    )
    (net (code "3") (name "+12V_IN") (class "Default")
      (node (ref "D1") (pin "A") (pinfunction "A_A") (pintype "passive"))
      (node (ref "JP3") (pin "1") (pinfunction "1_1") (pintype "passive"))
      (node (ref "JP3") (pin "2") (pinfunction "2_2") (pintype "passive"))
    )
    (net (code "4") (name "-12V") (class "Default")
      (node (ref "C20") (pin "2") (pinfunction "2_2") (pintype "passive"))
      (node (ref "C5") (pin "-") (pinfunction "-_-") (pintype "passive"))
      (node (ref "C7") (pin "2") (pinfunction "2_2") (pintype "passive"))
      (node (ref "C9") (pin "2") (pinfunction "2_2") (pintype "passive"))
      (node (ref "D2") (pin "A") (pinfunction "A_A") (pintype "passive"))
      (node (ref "IC3") (pin "11") (pinfunction "V-_11") (pintype "power_in"))
      (node (ref "IC4") (pin "11") (pinfunction "V-_11") (pintype "power_in"))
    )
    (net (code "5") (name "-12V_IN") (class "Default")
      (node (ref "D2") (pin "C") (pinfunction "C_C") (pintype "passive"))
      (node (ref "JP3") (pin "10") (pinfunction "10_10") (pintype "passive"))
      (node (ref "JP3") (pin "9") (pinfunction "9_9") (pintype "passive"))
    )
    (net (code "6") (name "AGND") (class "Default")
      (node (ref "C1") (pin "2") (pinfunction "2_2") (pintype "passive"))
      (node (ref "C10") (pin "2") (pinfunction "2_2") (pintype "passive"))
      (node (ref "C11") (pin "2") (pinfunction "2_2") (pintype "passive"))
      (node (ref "C12") (pin "2") (pinfunction "2_2") (pintype "passive"))
      (node (ref "C13") (pin "2") (pinfunction "2_2") (pintype "passive"))
      (node (ref "C14") (pin "2") (pinfunction "2_2") (pintype "passive"))
      (node (ref "C15") (pin "2") (pinfunction "2_2") (pintype "passive"))
      (node (ref "C16") (pin "2") (pinfunction "2_2") (pintype "passive"))
      (node (ref "C17") (pin "2") (pinfunction "2_2") (pintype "passive"))
      (node (ref "C18") (pin "2") (pinfunction "2_2") (pintype "passive"))
      (node (ref "C19") (pin "2") (pinfunction "2_2") (pintype "passive"))
      (node (ref "C2") (pin "2") (pinfunction "2_2") (pintype "passive"))
      (node (ref "C20") (pin "1") (pinfunction "1_1") (pintype "passive"))
      (node (ref "C21") (pin "2") (pinfunction "2_2") (pintype "passive"))
      (node (ref "C24") (pin "2") (pinfunction "2_2") (pintype "passive"))
      (node (ref "C25") (pin "2") (pinfunction "2_2") (pintype "passive"))
      (node (ref "C26") (pin "2") (pinfunction "2_2") (pintype "passive"))
      (node (ref "C27") (pin "2") (pinfunction "2_2") (pintype "passive"))
      (node (ref "C28") (pin "2") (pinfunction "2_2") (pintype "passive"))
      (node (ref "C3") (pin "2") (pinfunction "2_2") (pintype "passive"))
      (node (ref "C4") (pin "-") (pinfunction "-_-") (pintype "passive"))
      (node (ref "C5") (pin "+") (pinfunction "+_+") (pintype "passive"))
      (node (ref "C6") (pin "2") (pinfunction "2_2") (pintype "passive"))
      (node (ref "C7") (pin "1") (pinfunction "1_1") (pintype "passive"))
      (node (ref "C8") (pin "-") (pinfunction "-_-") (pintype "passive"))
      (node (ref "C9") (pin "1") (pinfunction "1_1") (pintype "passive"))
      (node (ref "IC1") (pin "1") (pinfunction "GROUND_1") (pintype "bidirectional"))
      (node (ref "IC2") (pin "5") (pinfunction "~{LDAC}_5") (pintype "bidirectional"))
      (node (ref "IC2") (pin "7") (pinfunction "AVSS_7") (pintype "power_in"))
      (node (ref "IC5") (pin "8") (pinfunction "VSS_8") (pintype "power_in"))
      (node (ref "IC6") (pin "8") (pinfunction "VSS_8") (pintype "power_in"))
      (node (ref "IC7") (pin "8") (pinfunction "VSS_8") (pintype "power_in"))
      (node (ref "IC8") (pin "8") (pinfunction "VSS_8") (pintype "power_in"))
      (node (ref "J10") (pin "3") (pinfunction "1_3") (pintype "passive"))
      (node (ref "J11") (pin "3") (pinfunction "1_3") (pintype "passive"))
      (node (ref "J12") (pin "3") (pinfunction "1_3") (pintype "passive"))
      (node (ref "J13") (pin "3") (pinfunction "1_3") (pintype "passive"))
      (node (ref "J14") (pin "3") (pinfunction "1_3") (pintype "passive"))
      (node (ref "J15") (pin "3") (pinfunction "1_3") (pintype "passive"))
      (node (ref "J16") (pin "3") (pinfunction "1_3") (pintype "passive"))
      (node (ref "J17") (pin "3") (pinfunction "1_3") (pintype "passive"))
      (node (ref "J18") (pin "3") (pinfunction "1_3") (pintype "passive"))
      (node (ref "J19") (pin "3") (pinfunction "1_3") (pintype "passive"))
      (node (ref "J2") (pin "3") (pinfunction "1_3") (pintype "passive"))
      (node (ref "J3") (pin "3") (pinfunction "1_3") (pintype "passive"))
      (node (ref "J4") (pin "3") (pinfunction "1_3") (pintype "passive"))
      (node (ref "J5") (pin "3") (pinfunction "1_3") (pintype "passive"))
      (node (ref "J6") (pin "3") (pinfunction "1_3") (pintype "passive"))
      (node (ref "J7") (pin "3") (pinfunction "1_3") (pintype "passive"))
      (node (ref "J8") (pin "3") (pinfunction "1_3") (pintype "passive"))
      (node (ref "J9") (pin "3") (pinfunction "1_3") (pintype "passive"))
      (node (ref "JP1") (pin "6") (pinfunction "6_6") (pintype "passive"))
      (node (ref "JP21") (pin "1") (pinfunction "1_1") (pintype "passive"))
      (node (ref "JP21") (pin "2") (pinfunction "2_2") (pintype "passive"))
      (node (ref "JP22") (pin "1") (pinfunction "1_1") (pintype "passive"))
      (node (ref "JP22") (pin "2") (pinfunction "2_2") (pintype "passive"))
      (node (ref "JP3") (pin "3") (pinfunction "3_3") (pintype "passive"))
      (node (ref "JP3") (pin "4") (pinfunction "4_4") (pintype "passive"))
      (node (ref "JP3") (pin "5") (pinfunction "5_5") (pintype "passive"))
      (node (ref "JP3") (pin "6") (pinfunction "6_6") (pintype "passive"))
      (node (ref "JP3") (pin "7") (pinfunction "7_7") (pintype "passive"))
      (node (ref "JP3") (pin "8") (pinfunction "8_8") (pintype "passive"))
      (node (ref "JP4") (pin "1") (pinfunction "1_1") (pintype "passive"))
      (node (ref "LED1") (pin "C") (pinfunction "C_C") (pintype "passive"))
      (node (ref "LED10") (pin "C") (pinfunction "C_C") (pintype "passive"))
      (node (ref "LED11") (pin "C") (pinfunction "C_C") (pintype "passive"))
      (node (ref "LED12") (pin "C") (pinfunction "C_C") (pintype "passive"))
      (node (ref "LED13") (pin "C") (pinfunction "C_C") (pintype "passive"))
      (node (ref "LED14") (pin "C") (pinfunction "C_C") (pintype "passive"))
      (node (ref "LED15") (pin "C") (pinfunction "C_C") (pintype "passive"))
      (node (ref "LED16") (pin "C") (pinfunction "C_C") (pintype "passive"))
      (node (ref "LED17") (pin "C") (pinfunction "C_C") (pintype "passive"))
      (node (ref "LED18") (pin "C") (pinfunction "C_C") (pintype "passive"))
      (node (ref "LED2") (pin "C") (pinfunction "C_C") (pintype "passive"))
      (node (ref "LED3") (pin "C") (pinfunction "C_C") (pintype "passive"))
      (node (ref "LED4") (pin "C") (pinfunction "C_C") (pintype "passive"))
      (node (ref "LED5") (pin "C") (pinfunction "C_C") (pintype "passive"))
      (node (ref "LED6") (pin "C") (pinfunction "C_C") (pintype "passive"))
      (node (ref "LED7") (pin "C") (pinfunction "C_C") (pintype "passive"))
      (node (ref "LED8") (pin "C") (pinfunction "C_C") (pintype "passive"))
      (node (ref "LED9") (pin "C") (pinfunction "C_C") (pintype "passive"))
      (node (ref "OK1") (pin "5") (pinfunction "GND_5") (pintype "passive"))
      (node (ref "R13") (pin "1") (pinfunction "1_1") (pintype "passive"))
      (node (ref "R33") (pin "1") (pinfunction "1_1") (pintype "passive"))
      (node (ref "R34") (pin "1") (pinfunction "1_1") (pintype "passive"))
      (node (ref "R35") (pin "1") (pinfunction "1_1") (pintype "passive"))
      (node (ref "R36") (pin "1") (pinfunction "1_1") (pintype "passive"))
      (node (ref "R8") (pin "1") (pinfunction "1_1") (pintype "passive"))
      (node (ref "U1") (pin "22") (pinfunction "GND_22") (pintype "bidirectional"))
      (node (ref "U1") (pin "8") (pinfunction "GND_8") (pintype "bidirectional"))
    )
    (net (code "7") (name "CH_1_ANA_1") (class "Default")
      (node (ref "IC7") (pin "3") (pinfunction "I_3") (pintype "input"))
      (node (ref "R19") (pin "2") (pinfunction "2_2") (pintype "passive"))
      (node (ref "U1") (pin "12") (pinfunction "PD6(AIN0)_12") (pintype "bidirectional"))
    )
    (net (code "8") (name "CH_1_ANA_2") (class "Default")
      (node (ref "IC7") (pin "5") (pinfunction "I_5") (pintype "input"))
      (node (ref "R20") (pin "2") (pinfunction "2_2") (pintype "passive"))
      (node (ref "U1") (pin "15") (pinfunction "PB1(OC1A)_15") (pintype "bidirectional"))
    )
    (net (code "9") (name "CH_1_DIGI_1") (class "Default")
      (node (ref "IC6") (pin "3") (pinfunction "I_3") (pintype "input"))
      (node (ref "JP17") (pin "6") (pinfunction "6_6") (pintype "passive"))
      (node (ref "U1") (pin "28") (pinfunction "PC5(ADC5/SCL)_28") (pintype "bidirectional"))
    )
    (net (code "10") (name "CH_1_DIGI_2") (class "Default")
      (node (ref "IC6") (pin "5") (pinfunction "I_5") (pintype "input"))
      (node (ref "JP17") (pin "5") (pinfunction "5_5") (pintype "passive"))
      (node (ref "U1") (pin "27") (pinfunction "PC4(ADC4/SDA)_27") (pintype "bidirectional"))
    )
    (net (code "11") (name "CH_1_DIGI_3") (class "Default")
      (node (ref "IC6") (pin "7") (pinfunction "I_7") (pintype "input"))
      (node (ref "JP17") (pin "4") (pinfunction "4_4") (pintype "passive"))
      (node (ref "U1") (pin "26") (pinfunction "PC3(ADC3)_26") (pintype "bidirectional"))
    )
    (net (code "12") (name "CH_2_ANA_1") (class "Default")
      (node (ref "IC7") (pin "7") (pinfunction "I_7") (pintype "input"))
      (node (ref "R21") (pin "2") (pinfunction "2_2") (pintype "passive"))
      (node (ref "U1") (pin "11") (pinfunction "PD5(T1)_11") (pintype "bidirectional"))
    )
    (net (code "13") (name "CH_2_ANA_2") (class "Default")
      (node (ref "IC7") (pin "9") (pinfunction "I_9") (pintype "input"))
      (node (ref "R22") (pin "2") (pinfunction "2_2") (pintype "passive"))
      (node (ref "U1") (pin "16") (pinfunction "PB2(SS/OC1B)_16") (pintype "bidirectional"))
    )
    (net (code "14") (name "CH_2_DIGI_1") (class "Default")
      (node (ref "IC6") (pin "9") (pinfunction "I_9") (pintype "input"))
      (node (ref "JP18") (pin "6") (pinfunction "6_6") (pintype "passive"))
      (node (ref "U1") (pin "25") (pinfunction "PC2(ADC2)_25") (pintype "bidirectional"))
    )
    (net (code "15") (name "CH_2_DIGI_2") (class "Default")
      (node (ref "IC6") (pin "11") (pinfunction "I_11") (pintype "input"))
      (node (ref "JP18") (pin "5") (pinfunction "5_5") (pintype "passive"))
      (node (ref "U1") (pin "24") (pinfunction "PC1(ADC1)_24") (pintype "bidirectional"))
    )
    (net (code "16") (name "CH_2_DIGI_3") (class "Default")
      (node (ref "IC6") (pin "14") (pinfunction "I_14") (pintype "input"))
      (node (ref "JP18") (pin "4") (pinfunction "4_4") (pintype "passive"))
      (node (ref "U1") (pin "23") (pinfunction "PC0(ADC0)_23") (pintype "bidirectional"))
    )
    (net (code "17") (name "GATE{slash}TRIG_1") (class "Default")
      (node (ref "C22") (pin "1") (pinfunction "1_1") (pintype "passive"))
      (node (ref "IC5") (pin "7") (pinfunction "I_7") (pintype "input"))
      (node (ref "U1") (pin "13") (pinfunction "PD7(AIN1)_13") (pintype "bidirectional"))
    )
    (net (code "18") (name "GATE{slash}TRIG_2") (class "Default")
      (node (ref "C23") (pin "1") (pinfunction "1_1") (pintype "passive"))
      (node (ref "IC5") (pin "9") (pinfunction "I_9") (pintype "input"))
      (node (ref "U1") (pin "14") (pinfunction "PB0(ICP)_14") (pintype "bidirectional"))
    )
    (net (code "19") (name "ICSP_MOSI") (class "Default")
      (node (ref "JP1") (pin "4") (pinfunction "4_4") (pintype "passive"))
      (node (ref "JP2") (pin "1") (pinfunction "1_1") (pintype "passive"))
    )
    (net (code "20") (name "ICSP_RST") (class "Default")
      (node (ref "JP1") (pin "5") (pinfunction "5_5") (pintype "passive"))
      (node (ref "R1") (pin "1") (pinfunction "1_1") (pintype "passive"))
      (node (ref "U1") (pin "1") (pinfunction "PC6(/RESET)_1") (pintype "bidirectional"))
    )
    (net (code "21") (name "ICSP_SCK") (class "Default")
      (node (ref "JP1") (pin "3") (pinfunction "3_3") (pintype "passive"))
      (node (ref "JP2") (pin "2") (pinfunction "2_2") (pintype "passive"))
    )
    (net (code "22") (name "MCP4822_A") (class "Default")
      (node (ref "IC2") (pin "8") (pinfunction "VOUTA_8") (pintype "output"))
      (node (ref "IC3") (pin "10") (pinfunction "+IN_10") (pintype "input"))
    )
    (net (code "23") (name "MCP4822_B") (class "Default")
      (node (ref "IC2") (pin "6") (pinfunction "VOUTB_6") (pintype "output"))
      (node (ref "IC3") (pin "12") (pinfunction "+IN_12") (pintype "input"))
    )
    (net (code "24") (name "MCP4822_CS") (class "Default")
      (node (ref "IC2") (pin "2") (pinfunction "~{CS}_2") (pintype "input"))
      (node (ref "U1") (pin "6") (pinfunction "PD4(XCK/T0)_6") (pintype "bidirectional"))
    )
    (net (code "25") (name "MCP4822_MOSI") (class "Default")
      (node (ref "IC2") (pin "4") (pinfunction "SDI_4") (pintype "bidirectional"))
      (node (ref "JP2") (pin "5") (pinfunction "5_5") (pintype "passive"))
    )
    (net (code "26") (name "MCP4822_SCK") (class "Default")
      (node (ref "IC2") (pin "3") (pinfunction "SCK_3") (pintype "bidirectional"))
      (node (ref "JP2") (pin "6") (pinfunction "6_6") (pintype "passive"))
    )
    (net (code "27") (name "MIDI_CLK") (class "Default")
      (node (ref "IC5") (pin "3") (pinfunction "I_3") (pintype "input"))
      (node (ref "JP15") (pin "2") (pinfunction "2_2") (pintype "passive"))
      (node (ref "U1") (pin "4") (pinfunction "PD2(INT0)_4") (pintype "bidirectional"))
    )
    (net (code "28") (name "MIDI_CLK_RST") (class "Default")
      (node (ref "IC5") (pin "5") (pinfunction "I_5") (pintype "input"))
      (node (ref "JP15") (pin "3") (pinfunction "3_3") (pintype "passive"))
      (node (ref "U1") (pin "5") (pinfunction "PD3(INT1)_5") (pintype "bidirectional"))
    )
    (net (code "29") (name "MIDI_IN") (class "Default")
      (node (ref "OK1") (pin "6") (pinfunction "VO_6") (pintype "passive"))
      (node (ref "R3") (pin "2") (pinfunction "2_2") (pintype "passive"))
      (node (ref "U1") (pin "2") (pinfunction "PD0(RXD)_2") (pintype "bidirectional"))
    )
    (net (code "30") (name "MISO") (class "Default")
      (node (ref "JP1") (pin "1") (pinfunction "1_1") (pintype "passive"))
      (node (ref "U1") (pin "18") (pinfunction "PB4(MISO)_18") (pintype "bidirectional"))
    )
    (net (code "31") (name "MOSI") (class "Default")
      (node (ref "JP2") (pin "3") (pinfunction "3_3") (pintype "passive"))
      (node (ref "U1") (pin "17") (pinfunction "PB3(MOSI/OC2)_17") (pintype "bidirectional"))
    )
    (net (code "32") (name "Net-(C12-Pad1)") (class "Default")
      (node (ref "C12") (pin "1") (pinfunction "1_1") (pintype "passive"))
      (node (ref "R19") (pin "1") (pinfunction "1_1") (pintype "passive"))
      (node (ref "R23") (pin "2") (pinfunction "2_2") (pintype "passive"))
    )
    (net (code "33") (name "Net-(C13-Pad1)") (class "Default")
      (node (ref "C13") (pin "1") (pinfunction "1_1") (pintype "passive"))
      (node (ref "R20") (pin "1") (pinfunction "1_1") (pintype "passive"))
      (node (ref "R24") (pin "2") (pinfunction "2_2") (pintype "passive"))
    )
    (net (code "34") (name "Net-(C14-Pad1)") (class "Default")
      (node (ref "C14") (pin "1") (pinfunction "1_1") (pintype "passive"))
      (node (ref "R21") (pin "1") (pinfunction "1_1") (pintype "passive"))
      (node (ref "R25") (pin "2") (pinfunction "2_2") (pintype "passive"))
    )
    (net (code "35") (name "Net-(C15-Pad1)") (class "Default")
      (node (ref "C15") (pin "1") (pinfunction "1_1") (pintype "passive"))
      (node (ref "R22") (pin "1") (pinfunction "1_1") (pintype "passive"))
      (node (ref "R26") (pin "2") (pinfunction "2_2") (pintype "passive"))
    )
    (net (code "36") (name "Net-(D4-PadA)") (class "Default")
      (node (ref "D4") (pin "A") (pinfunction "A_A") (pintype "passive"))
      (node (ref "R33") (pin "2") (pinfunction "2_2") (pintype "passive"))
    )
    (net (code "37") (name "Net-(D5-PadA)") (class "Default")
      (node (ref "D5") (pin "A") (pinfunction "A_A") (pintype "passive"))
      (node (ref "R34") (pin "2") (pinfunction "2_2") (pintype "passive"))
    )
    (net (code "38") (name "Net-(IC3A-+IN)") (class "Default")
      (node (ref "IC3") (pin "3") (pinfunction "+IN_3") (pintype "input"))
      (node (ref "JP7") (pin "2") (pinfunction "2_2") (pintype "passive"))
      (node (ref "R5") (pin "1") (pinfunction "1_1") (pintype "passive"))
      (node (ref "R6") (pin "2") (pinfunction "2_2") (pintype "passive"))
    )
    (net (code "39") (name "Net-(IC3A--IN)") (class "Default")
      (node (ref "IC3") (pin "1") (pinfunction "OUT_1") (pintype "output"))
      (node (ref "IC3") (pin "2") (pinfunction "-IN_2") (pintype "input"))
      (node (ref "JP7") (pin "1") (pinfunction "1_1") (pintype "passive"))
    )
    (net (code "40") (name "Net-(IC3B-+IN)") (class "Default")
      (node (ref "IC3") (pin "5") (pinfunction "+IN_5") (pintype "input"))
      (node (ref "JP7") (pin "4") (pinfunction "4_4") (pintype "passive"))
      (node (ref "R10") (pin "1") (pinfunction "1_1") (pintype "passive"))
      (node (ref "R11") (pin "2") (pinfunction "2_2") (pintype "passive"))
    )
    (net (code "41") (name "Net-(IC3B--IN)") (class "Default")
      (node (ref "IC3") (pin "6") (pinfunction "-IN_6") (pintype "input"))
      (node (ref "IC3") (pin "7") (pinfunction "OUT_7") (pintype "output"))
      (node (ref "JP7") (pin "3") (pinfunction "3_3") (pintype "passive"))
    )
    (net (code "42") (name "Net-(IC3C--IN)") (class "Default")
      (node (ref "IC3") (pin "9") (pinfunction "-IN_9") (pintype "input"))
      (node (ref "R7") (pin "2") (pinfunction "WIPER_2") (pintype "bidirectional"))
    )
    (net (code "43") (name "Net-(IC3C-OUT)") (class "Default")
      (node (ref "IC3") (pin "8") (pinfunction "OUT_8") (pintype "output"))
      (node (ref "R5") (pin "2") (pinfunction "2_2") (pintype "passive"))
    )
    (net (code "44") (name "Net-(IC3D--IN)") (class "Default")
      (node (ref "IC3") (pin "13") (pinfunction "-IN_13") (pintype "input"))
      (node (ref "R12") (pin "2") (pinfunction "WIPER_2") (pintype "bidirectional"))
    )
    (net (code "45") (name "Net-(IC3D-OUT)") (class "Default")
      (node (ref "IC3") (pin "14") (pinfunction "OUT_14") (pintype "output"))
      (node (ref "R10") (pin "2") (pinfunction "2_2") (pintype "passive"))
    )
    (net (code "46") (name "Net-(IC4A-+IN)") (class "Default")
      (node (ref "C16") (pin "1") (pinfunction "1_1") (pintype "passive"))
      (node (ref "IC4") (pin "3") (pinfunction "+IN_3") (pintype "input"))
      (node (ref "R23") (pin "1") (pinfunction "1_1") (pintype "passive"))
    )
    (net (code "47") (name "Net-(IC4A--IN)") (class "Default")
      (node (ref "IC4") (pin "2") (pinfunction "-IN_2") (pintype "input"))
      (node (ref "JP9") (pin "3") (pinfunction "3_3") (pintype "passive"))
      (node (ref "R27") (pin "1") (pinfunction "1_1") (pintype "passive"))
    )
    (net (code "48") (name "Net-(IC4A-OUT)") (class "Default")
      (node (ref "IC4") (pin "1") (pinfunction "OUT_1") (pintype "output"))
      (node (ref "R27") (pin "2") (pinfunction "2_2") (pintype "passive"))
    )
    (net (code "49") (name "Net-(IC4B-+IN)") (class "Default")
      (node (ref "C17") (pin "1") (pinfunction "1_1") (pintype "passive"))
      (node (ref "IC4") (pin "5") (pinfunction "+IN_5") (pintype "input"))
      (node (ref "R24") (pin "1") (pinfunction "1_1") (pintype "passive"))
    )
    (net (code "50") (name "Net-(IC4B--IN)") (class "Default")
      (node (ref "IC4") (pin "6") (pinfunction "-IN_6") (pintype "input"))
      (node (ref "JP9") (pin "4") (pinfunction "4_4") (pintype "passive"))
      (node (ref "R28") (pin "1") (pinfunction "1_1") (pintype "passive"))
    )
    (net (code "51") (name "Net-(IC4B-OUT)") (class "Default")
      (node (ref "IC4") (pin "7") (pinfunction "OUT_7") (pintype "output"))
      (node (ref "R28") (pin "2") (pinfunction "2_2") (pintype "passive"))
    )
    (net (code "52") (name "Net-(IC4C-+IN)") (class "Default")
      (node (ref "C18") (pin "1") (pinfunction "1_1") (pintype "passive"))
      (node (ref "IC4") (pin "10") (pinfunction "+IN_10") (pintype "input"))
      (node (ref "R25") (pin "1") (pinfunction "1_1") (pintype "passive"))
    )
    (net (code "53") (name "Net-(IC4C--IN)") (class "Default")
      (node (ref "IC4") (pin "9") (pinfunction "-IN_9") (pintype "input"))
      (node (ref "JP11") (pin "3") (pinfunction "3_3") (pintype "passive"))
      (node (ref "R29") (pin "1") (pinfunction "1_1") (pintype "passive"))
    )
    (net (code "54") (name "Net-(IC4C-OUT)") (class "Default")
      (node (ref "IC4") (pin "8") (pinfunction "OUT_8") (pintype "output"))
      (node (ref "R29") (pin "2") (pinfunction "2_2") (pintype "passive"))
    )
    (net (code "55") (name "Net-(IC4D-+IN)") (class "Default")
      (node (ref "C19") (pin "1") (pinfunction "1_1") (pintype "passive"))
      (node (ref "IC4") (pin "12") (pinfunction "+IN_12") (pintype "input"))
      (node (ref "R26") (pin "1") (pinfunction "1_1") (pintype "passive"))
    )
    (net (code "56") (name "Net-(IC4D--IN)") (class "Default")
      (node (ref "IC4") (pin "13") (pinfunction "-IN_13") (pintype "input"))
      (node (ref "JP11") (pin "4") (pinfunction "4_4") (pintype "passive"))
      (node (ref "R30") (pin "1") (pinfunction "1_1") (pintype "passive"))
    )
    (net (code "57") (name "Net-(IC4D-OUT)") (class "Default")
      (node (ref "IC4") (pin "14") (pinfunction "OUT_14") (pintype "output"))
      (node (ref "R30") (pin "2") (pinfunction "2_2") (pintype "passive"))
    )
    (net (code "58") (name "Net-(IC5A-O)") (class "Default")
      (node (ref "IC5") (pin "2") (pinfunction "O_2") (pintype "output"))
      (node (ref "JP15") (pin "1") (pinfunction "1_1") (pintype "passive"))
    )
    (net (code "59") (name "Net-(IC5B-O)") (class "Default")
      (node (ref "IC5") (pin "4") (pinfunction "O_4") (pintype "output"))
      (node (ref "JP15") (pin "4") (pinfunction "4_4") (pintype "passive"))
    )
    (net (code "60") (name "Net-(IC5C-O)") (class "Default")
      (node (ref "IC5") (pin "6") (pinfunction "O_6") (pintype "output"))
      (node (ref "JP13") (pin "2") (pinfunction "2_2") (pintype "passive"))
    )
    (net (code "61") (name "Net-(IC5D-O)") (class "Default")
      (node (ref "IC5") (pin "10") (pinfunction "O_10") (pintype "output"))
      (node (ref "JP13") (pin "3") (pinfunction "3_3") (pintype "passive"))
    )
    (net (code "62") (name "Net-(IC5E-I)") (class "Default")
      (node (ref "C22") (pin "2") (pinfunction "2_2") (pintype "passive"))
      (node (ref "D4") (pin "C") (pinfunction "C_C") (pintype "passive"))
      (node (ref "IC5") (pin "11") (pinfunction "I_11") (pintype "input"))
      (node (ref "R35") (pin "2") (pinfunction "2_2") (pintype "passive"))
    )
    (net (code "63") (name "Net-(IC5E-O)") (class "Default")
      (node (ref "IC5") (pin "12") (pinfunction "O_12") (pintype "output"))
      (node (ref "JP13") (pin "1") (pinfunction "1_1") (pintype "passive"))
    )
    (net (code "64") (name "Net-(IC5F-I)") (class "Default")
      (node (ref "C23") (pin "2") (pinfunction "2_2") (pintype "passive"))
      (node (ref "D5") (pin "C") (pinfunction "C_C") (pintype "passive"))
      (node (ref "IC5") (pin "14") (pinfunction "I_14") (pintype "input"))
      (node (ref "R36") (pin "2") (pinfunction "2_2") (pintype "passive"))
    )
    (net (code "65") (name "Net-(IC5F-O)") (class "Default")
      (node (ref "IC5") (pin "15") (pinfunction "O_15") (pintype "output"))
      (node (ref "JP13") (pin "4") (pinfunction "4_4") (pintype "passive"))
    )
    (net (code "66") (name "Net-(IC6A-O)") (class "Default")
      (node (ref "IC6") (pin "2") (pinfunction "O_2") (pintype "output"))
      (node (ref "JP17") (pin "1") (pinfunction "1_1") (pintype "passive"))
    )
    (net (code "67") (name "Net-(IC6B-O)") (class "Default")
      (node (ref "IC6") (pin "4") (pinfunction "O_4") (pintype "output"))
      (node (ref "JP17") (pin "3") (pinfunction "3_3") (pintype "passive"))
    )
    (net (code "68") (name "Net-(IC6C-O)") (class "Default")
      (node (ref "IC6") (pin "6") (pinfunction "O_6") (pintype "output"))
      (node (ref "JP17") (pin "2") (pinfunction "2_2") (pintype "passive"))
    )
    (net (code "69") (name "Net-(IC6D-O)") (class "Default")
      (node (ref "IC6") (pin "10") (pinfunction "O_10") (pintype "output"))
      (node (ref "JP18") (pin "1") (pinfunction "1_1") (pintype "passive"))
    )
    (net (code "70") (name "Net-(IC6E-O)") (class "Default")
      (node (ref "IC6") (pin "12") (pinfunction "O_12") (pintype "output"))
      (node (ref "JP18") (pin "3") (pinfunction "3_3") (pintype "passive"))
    )
    (net (code "71") (name "Net-(IC6F-O)") (class "Default")
      (node (ref "IC6") (pin "15") (pinfunction "O_15") (pintype "output"))
      (node (ref "JP18") (pin "2") (pinfunction "2_2") (pintype "passive"))
    )
    (net (code "72") (name "Net-(IC7A-O)") (class "Default")
      (node (ref "IC7") (pin "2") (pinfunction "O_2") (pintype "output"))
      (node (ref "JP9") (pin "1") (pinfunction "1_1") (pintype "passive"))
    )
    (net (code "73") (name "Net-(IC7B-O)") (class "Default")
      (node (ref "IC7") (pin "4") (pinfunction "O_4") (pintype "output"))
      (node (ref "JP9") (pin "2") (pinfunction "2_2") (pintype "passive"))
    )
    (net (code "74") (name "Net-(IC7C-O)") (class "Default")
      (node (ref "IC7") (pin "6") (pinfunction "O_6") (pintype "output"))
      (node (ref "JP11") (pin "1") (pinfunction "1_1") (pintype "passive"))
    )
    (net (code "75") (name "Net-(IC7D-O)") (class "Default")
      (node (ref "IC7") (pin "10") (pinfunction "O_10") (pintype "output"))
      (node (ref "JP11") (pin "2") (pinfunction "2_2") (pintype "passive"))
    )
    (net (code "76") (name "Net-(IC8A-I)") (class "Default")
      (node (ref "IC8") (pin "3") (pinfunction "I_3") (pintype "input"))
      (node (ref "JP14") (pin "2") (pinfunction "2_2") (pintype "passive"))
      (node (ref "R41") (pin "2") (pinfunction "2_2") (pintype "passive"))
    )
    (net (code "77") (name "Net-(IC8A-O)") (class "Default")
      (node (ref "IC8") (pin "2") (pinfunction "O_2") (pintype "output"))
      (node (ref "R37") (pin "2") (pinfunction "2_2") (pintype "passive"))
    )
    (net (code "78") (name "Net-(IC8B-I)") (class "Default")
      (node (ref "IC8") (pin "5") (pinfunction "I_5") (pintype "input"))
      (node (ref "JP14") (pin "3") (pinfunction "3_3") (pintype "passive"))
      (node (ref "R43") (pin "2") (pinfunction "2_2") (pintype "passive"))
    )
    (net (code "79") (name "Net-(IC8B-O)") (class "Default")
      (node (ref "IC8") (pin "4") (pinfunction "O_4") (pintype "output"))
      (node (ref "R39") (pin "2") (pinfunction "2_2") (pintype "passive"))
    )
    (net (code "80") (name "Net-(IC8C-I)") (class "Default")
      (node (ref "IC8") (pin "7") (pinfunction "I_7") (pintype "input"))
      (node (ref "JP14") (pin "4") (pinfunction "4_4") (pintype "passive"))
      (node (ref "R44") (pin "2") (pinfunction "2_2") (pintype "passive"))
    )
    (net (code "81") (name "Net-(IC8C-O)") (class "Default")
      (node (ref "IC8") (pin "6") (pinfunction "O_6") (pintype "output"))
      (node (ref "R40") (pin "2") (pinfunction "2_2") (pintype "passive"))
    )
    (net (code "82") (name "Net-(IC8D-I)") (class "Default")
      (node (ref "IC8") (pin "9") (pinfunction "I_9") (pintype "input"))
      (node (ref "JP14") (pin "1") (pinfunction "1_1") (pintype "passive"))
      (node (ref "R42") (pin "2") (pinfunction "2_2") (pintype "passive"))
    )
    (net (code "83") (name "Net-(IC8D-O)") (class "Default")
      (node (ref "IC8") (pin "10") (pinfunction "O_10") (pintype "output"))
      (node (ref "R38") (pin "2") (pinfunction "2_2") (pintype "passive"))
    )
    (net (code "84") (name "Net-(IC8G-VDD)") (class "Default")
      (node (ref "C28") (pin "1") (pinfunction "1_1") (pintype "passive"))
      (node (ref "IC8") (pin "1") (pinfunction "VDD_1") (pintype "power_in"))
      (node (ref "JP14") (pin "5") (pinfunction "5_5") (pintype "passive"))
    )
    (net (code "85") (name "Net-(J1-Pad1)") (class "Default")
      (node (ref "J1") (pin "1") (pinfunction "1_1") (pintype "passive"))
      (node (ref "JP4") (pin "2") (pinfunction "2_2") (pintype "passive"))
    )
    (net (code "86") (name "Net-(J1-Pad2)") (class "Default")
      (node (ref "J1") (pin "2") (pinfunction "2_2") (pintype "passive"))
      (node (ref "JP6") (pin "1") (pinfunction "1_1") (pintype "passive"))
    )
    (net (code "87") (name "Net-(J1-Pad3)") (class "Default")
      (node (ref "J1") (pin "3") (pinfunction "3_3") (pintype "passive"))
      (node (ref "R4") (pin "1") (pinfunction "1_1") (pintype "passive"))
    )
    (net (code "88") (name "Net-(J2-2)") (class "Default")
      (node (ref "J2") (pin "1") (pinfunction "2_1") (pintype "passive"))
      (node (ref "JP8") (pin "2") (pinfunction "2_2") (pintype "passive"))
    )
    (net (code "89") (name "Net-(J3-2)") (class "Default")
      (node (ref "J3") (pin "1") (pinfunction "2_1") (pintype "passive"))
      (node (ref "JP8") (pin "4") (pinfunction "4_4") (pintype "passive"))
    )
    (net (code "90") (name "Net-(J4-2)") (class "Default")
      (node (ref "J4") (pin "1") (pinfunction "2_1") (pintype "passive"))
      (node (ref "JP10") (pin "3") (pinfunction "3_3") (pintype "passive"))
    )
    (net (code "91") (name "Net-(J5-2)") (class "Default")
      (node (ref "J5") (pin "1") (pinfunction "2_1") (pintype "passive"))
      (node (ref "JP10") (pin "4") (pinfunction "4_4") (pintype "passive"))
    )
    (net (code "92") (name "Net-(J6-2)") (class "Default")
      (node (ref "J6") (pin "1") (pinfunction "2_1") (pintype "passive"))
      (node (ref "JP12") (pin "3") (pinfunction "3_3") (pintype "passive"))
    )
    (net (code "93") (name "Net-(J7-2)") (class "Default")
      (node (ref "J7") (pin "1") (pinfunction "2_1") (pintype "passive"))
      (node (ref "JP12") (pin "4") (pinfunction "4_4") (pintype "passive"))
    )
    (net (code "94") (name "Net-(J8-2)") (class "Default")
      (node (ref "J8") (pin "1") (pinfunction "2_1") (pintype "passive"))
      (node (ref "R41") (pin "1") (pinfunction "1_1") (pintype "passive"))
    )
    (net (code "95") (name "Net-(J9-2)") (class "Default")
      (node (ref "J9") (pin "1") (pinfunction "2_1") (pintype "passive"))
      (node (ref "R42") (pin "1") (pinfunction "1_1") (pintype "passive"))
    )
    (net (code "96") (name "Net-(J10-2)") (class "Default")
      (node (ref "J10") (pin "1") (pinfunction "2_1") (pintype "passive"))
      (node (ref "R43") (pin "1") (pinfunction "1_1") (pintype "passive"))
    )
    (net (code "97") (name "Net-(J11-2)") (class "Default")
      (node (ref "J11") (pin "1") (pinfunction "2_1") (pintype "passive"))
      (node (ref "R44") (pin "1") (pinfunction "1_1") (pintype "passive"))
    )
    (net (code "98") (name "Net-(J12-2)") (class "Default")
      (node (ref "J12") (pin "1") (pinfunction "2_1") (pintype "passive"))
      (node (ref "R45") (pin "1") (pinfunction "1_1") (pintype "passive"))
    )
    (net (code "99") (name "Net-(J13-2)") (class "Default")
      (node (ref "J13") (pin "1") (pinfunction "2_1") (pintype "passive"))
      (node (ref "R46") (pin "1") (pinfunction "1_1") (pintype "passive"))
    )
    (net (code "100") (name "Net-(J14-2)") (class "Default")
      (node (ref "J14") (pin "1") (pinfunction "2_1") (pintype "passive"))
      (node (ref "R53") (pin "1") (pinfunction "1_1") (pintype "passive"))
    )
    (net (code "101") (name "Net-(J15-2)") (class "Default")
      (node (ref "J15") (pin "1") (pinfunction "2_1") (pintype "passive"))
      (node (ref "R54") (pin "1") (pinfunction "1_1") (pintype "passive"))
    )
    (net (code "102") (name "Net-(J16-2)") (class "Default")
      (node (ref "J16") (pin "1") (pinfunction "2_1") (pintype "passive"))
      (node (ref "R55") (pin "1") (pinfunction "1_1") (pintype "passive"))
    )
    (net (code "103") (name "Net-(J17-2)") (class "Default")
      (node (ref "J17") (pin "1") (pinfunction "2_1") (pintype "passive"))
      (node (ref "R56") (pin "1") (pinfunction "1_1") (pintype "passive"))
    )
    (net (code "104") (name "Net-(J18-2)") (class "Default")
      (node (ref "J18") (pin "1") (pinfunction "2_1") (pintype "passive"))
      (node (ref "R57") (pin "1") (pinfunction "1_1") (pintype "passive"))
    )
    (net (code "105") (name "Net-(J19-2)") (class "Default")
      (node (ref "J19") (pin "1") (pinfunction "2_1") (pintype "passive"))
      (node (ref "R58") (pin "1") (pinfunction "1_1") (pintype "passive"))
    )
    (net (code "106") (name "Net-(JP6-Pad2)") (class "Default")
      (node (ref "JP6") (pin "2") (pinfunction "2_2") (pintype "passive"))
      (node (ref "R4") (pin "2") (pinfunction "2_2") (pintype "passive"))
    )
    (net (code "107") (name "Net-(JP8-Pad1)") (class "Default")
      (node (ref "JP8") (pin "1") (pinfunction "1_1") (pintype "passive"))
      (node (ref "R9") (pin "2") (pinfunction "2_2") (pintype "passive"))
    )
    (net (code "108") (name "Net-(JP8-Pad3)") (class "Default")
      (node (ref "JP8") (pin "3") (pinfunction "3_3") (pintype "passive"))
      (node (ref "R14") (pin "2") (pinfunction "2_2") (pintype "passive"))
    )
    (net (code "109") (name "Net-(JP10-Pad1)") (class "Default")
      (node (ref "JP10") (pin "1") (pinfunction "1_1") (pintype "passive"))
      (node (ref "R15") (pin "2") (pinfunction "2_2") (pintype "passive"))
    )
    (net (code "110") (name "Net-(JP10-Pad2)") (class "Default")
      (node (ref "JP10") (pin "2") (pinfunction "2_2") (pintype "passive"))
      (node (ref "R16") (pin "2") (pinfunction "2_2") (pintype "passive"))
    )
    (net (code "111") (name "Net-(JP12-Pad1)") (class "Default")
      (node (ref "JP12") (pin "1") (pinfunction "1_1") (pintype "passive"))
      (node (ref "R17") (pin "2") (pinfunction "2_2") (pintype "passive"))
    )
    (net (code "112") (name "Net-(JP12-Pad2)") (class "Default")
      (node (ref "JP12") (pin "2") (pinfunction "2_2") (pintype "passive"))
      (node (ref "R18") (pin "2") (pinfunction "2_2") (pintype "passive"))
    )
    (net (code "113") (name "Net-(JP16-Pad1)") (class "Default")
      (node (ref "JP16") (pin "1") (pinfunction "1_1") (pintype "passive"))
      (node (ref "R45") (pin "2") (pinfunction "2_2") (pintype "passive"))
    )
    (net (code "114") (name "Net-(JP16-Pad2)") (class "Default")
      (node (ref "JP16") (pin "2") (pinfunction "2_2") (pintype "passive"))
      (node (ref "R31") (pin "2") (pinfunction "2_2") (pintype "passive"))
    )
    (net (code "115") (name "Net-(JP16-Pad3)") (class "Default")
      (node (ref "JP16") (pin "3") (pinfunction "3_3") (pintype "passive"))
      (node (ref "R32") (pin "2") (pinfunction "2_2") (pintype "passive"))
    )
    (net (code "116") (name "Net-(JP16-Pad4)") (class "Default")
      (node (ref "JP16") (pin "4") (pinfunction "4_4") (pintype "passive"))
      (node (ref "R46") (pin "2") (pinfunction "2_2") (pintype "passive"))
    )
    (net (code "117") (name "Net-(JP19-Pad1)") (class "Default")
      (node (ref "JP19") (pin "1") (pinfunction "1_1") (pintype "passive"))
      (node (ref "R53") (pin "2") (pinfunction "2_2") (pintype "passive"))
    )
    (net (code "118") (name "Net-(JP19-Pad2)") (class "Default")
      (node (ref "JP19") (pin "2") (pinfunction "2_2") (pintype "passive"))
      (node (ref "R55") (pin "2") (pinfunction "2_2") (pintype "passive"))
    )
    (net (code "119") (name "Net-(JP19-Pad3)") (class "Default")
      (node (ref "JP19") (pin "3") (pinfunction "3_3") (pintype "passive"))
      (node (ref "R54") (pin "2") (pinfunction "2_2") (pintype "passive"))
    )
    (net (code "120") (name "Net-(JP19-Pad4)") (class "Default")
      (node (ref "JP19") (pin "4") (pinfunction "4_4") (pintype "passive"))
      (node (ref "R49") (pin "2") (pinfunction "2_2") (pintype "passive"))
    )
    (net (code "121") (name "Net-(JP19-Pad5)") (class "Default")
      (node (ref "JP19") (pin "5") (pinfunction "5_5") (pintype "passive"))
      (node (ref "R48") (pin "2") (pinfunction "2_2") (pintype "passive"))
    )
    (net (code "122") (name "Net-(JP19-Pad6)") (class "Default")
      (node (ref "JP19") (pin "6") (pinfunction "6_6") (pintype "passive"))
      (node (ref "R47") (pin "2") (pinfunction "2_2") (pintype "passive"))
    )
    (net (code "123") (name "Net-(JP20-Pad1)") (class "Default")
      (node (ref "JP20") (pin "1") (pinfunction "1_1") (pintype "passive"))
      (node (ref "R56") (pin "2") (pinfunction "2_2") (pintype "passive"))
    )
    (net (code "124") (name "Net-(JP20-Pad2)") (class "Default")
      (node (ref "JP20") (pin "2") (pinfunction "2_2") (pintype "passive"))
      (node (ref "R58") (pin "2") (pinfunction "2_2") (pintype "passive"))
    )
    (net (code "125") (name "Net-(JP20-Pad3)") (class "Default")
      (node (ref "JP20") (pin "3") (pinfunction "3_3") (pintype "passive"))
      (node (ref "R57") (pin "2") (pinfunction "2_2") (pintype "passive"))
    )
    (net (code "126") (name "Net-(JP20-Pad4)") (class "Default")
      (node (ref "JP20") (pin "4") (pinfunction "4_4") (pintype "passive"))
      (node (ref "R52") (pin "2") (pinfunction "2_2") (pintype "passive"))
    )
    (net (code "127") (name "Net-(JP20-Pad5)") (class "Default")
      (node (ref "JP20") (pin "5") (pinfunction "5_5") (pintype "passive"))
      (node (ref "R51") (pin "2") (pinfunction "2_2") (pintype "passive"))
    )
    (net (code "128") (name "Net-(JP20-Pad6)") (class "Default")
      (node (ref "JP20") (pin "6") (pinfunction "6_6") (pintype "passive"))
      (node (ref "R50") (pin "2") (pinfunction "2_2") (pintype "passive"))
    )
    (net (code "129") (name "Net-(LED1-PadA)") (class "Default")
      (node (ref "LED1") (pin "A") (pinfunction "A_A") (pintype "passive"))
      (node (ref "R9") (pin "1") (pinfunction "1_1") (pintype "passive"))
    )
    (net (code "130") (name "Net-(LED2-PadA)") (class "Default")
      (node (ref "LED2") (pin "A") (pinfunction "A_A") (pintype "passive"))
      (node (ref "R14") (pin "1") (pinfunction "1_1") (pintype "passive"))
    )
    (net (code "131") (name "Net-(LED3-PadA)") (class "Default")
      (node (ref "LED3") (pin "A") (pinfunction "A_A") (pintype "passive"))
      (node (ref "R15") (pin "1") (pinfunction "1_1") (pintype "passive"))
    )
    (net (code "132") (name "Net-(LED4-PadA)") (class "Default")
      (node (ref "LED4") (pin "A") (pinfunction "A_A") (pintype "passive"))
      (node (ref "R16") (pin "1") (pinfunction "1_1") (pintype "passive"))
    )
    (net (code "133") (name "Net-(LED5-PadA)") (class "Default")
      (node (ref "LED5") (pin "A") (pinfunction "A_A") (pintype "passive"))
      (node (ref "R17") (pin "1") (pinfunction "1_1") (pintype "passive"))
    )
    (net (code "134") (name "Net-(LED6-PadA)") (class "Default")
      (node (ref "LED6") (pin "A") (pinfunction "A_A") (pintype "passive"))
      (node (ref "R18") (pin "1") (pinfunction "1_1") (pintype "passive"))
    )
    (net (code "135") (name "Net-(LED7-PadA)") (class "Default")
      (node (ref "LED7") (pin "A") (pinfunction "A_A") (pintype "passive"))
      (node (ref "R31") (pin "1") (pinfunction "1_1") (pintype "passive"))
    )
    (net (code "136") (name "Net-(LED8-PadA)") (class "Default")
      (node (ref "LED8") (pin "A") (pinfunction "A_A") (pintype "passive"))
      (node (ref "R32") (pin "1") (pinfunction "1_1") (pintype "passive"))
    )
    (net (code "137") (name "Net-(LED9-PadA)") (class "Default")
      (node (ref "LED9") (pin "A") (pinfunction "A_A") (pintype "passive"))
      (node (ref "R37") (pin "1") (pinfunction "1_1") (pintype "passive"))
    )
    (net (code "138") (name "Net-(LED10-PadA)") (class "Default")
      (node (ref "LED10") (pin "A") (pinfunction "A_A") (pintype "passive"))
      (node (ref "R38") (pin "1") (pinfunction "1_1") (pintype "passive"))
    )
    (net (code "139") (name "Net-(LED11-PadA)") (class "Default")
      (node (ref "LED11") (pin "A") (pinfunction "A_A") (pintype "passive"))
      (node (ref "R39") (pin "1") (pinfunction "1_1") (pintype "passive"))
    )
    (net (code "140") (name "Net-(LED12-PadA)") (class "Default")
      (node (ref "LED12") (pin "A") (pinfunction "A_A") (pintype "passive"))
      (node (ref "R40") (pin "1") (pinfunction "1_1") (pintype "passive"))
    )
    (net (code "141") (name "Net-(LED13-PadA)") (class "Default")
      (node (ref "LED13") (pin "A") (pinfunction "A_A") (pintype "passive"))
      (node (ref "R47") (pin "1") (pinfunction "1_1") (pintype "passive"))
    )
    (net (code "142") (name "Net-(LED14-PadA)") (class "Default")
      (node (ref "LED14") (pin "A") (pinfunction "A_A") (pintype "passive"))
      (node (ref "R48") (pin "1") (pinfunction "1_1") (pintype "passive"))
    )
    (net (code "143") (name "Net-(LED15-PadA)") (class "Default")
      (node (ref "LED15") (pin "A") (pinfunction "A_A") (pintype "passive"))
      (node (ref "R49") (pin "1") (pinfunction "1_1") (pintype "passive"))
    )
    (net (code "144") (name "Net-(LED16-PadA)") (class "Default")
      (node (ref "LED16") (pin "A") (pinfunction "A_A") (pintype "passive"))
      (node (ref "R50") (pin "1") (pinfunction "1_1") (pintype "passive"))
    )
    (net (code "145") (name "Net-(LED17-PadA)") (class "Default")
      (node (ref "LED17") (pin "A") (pinfunction "A_A") (pintype "passive"))
      (node (ref "R51") (pin "1") (pinfunction "1_1") (pintype "passive"))
    )
    (net (code "146") (name "Net-(LED18-PadA)") (class "Default")
      (node (ref "LED18") (pin "A") (pinfunction "A_A") (pintype "passive"))
      (node (ref "R52") (pin "1") (pinfunction "1_1") (pintype "passive"))
    )
    (net (code "147") (name "Net-(OK1-A)") (class "Default")
      (node (ref "D3") (pin "C") (pinfunction "C_C") (pintype "passive"))
      (node (ref "JP5") (pin "2") (pinfunction "2_2") (pintype "passive"))
      (node (ref "OK1") (pin "2") (pinfunction "A_2") (pintype "passive"))
    )
    (net (code "148") (name "Net-(OK1-C)") (class "Default")
      (node (ref "D3") (pin "A") (pinfunction "A_A") (pintype "passive"))
      (node (ref "JP5") (pin "1") (pinfunction "1_1") (pintype "passive"))
      (node (ref "OK1") (pin "3") (pinfunction "C_3") (pintype "passive"))
    )
    (net (code "149") (name "Net-(R7-CCW)") (class "Default")
      (node (ref "R6") (pin "1") (pinfunction "1_1") (pintype "passive"))
      (node (ref "R7") (pin "1") (pinfunction "CCW_1") (pintype "bidirectional"))
    )
    (net (code "150") (name "Net-(R7-CW)") (class "Default")
      (node (ref "R7") (pin "3") (pinfunction "CW_3") (pintype "bidirectional"))
      (node (ref "R8") (pin "2") (pinfunction "2_2") (pintype "passive"))
    )
    (net (code "151") (name "Net-(R12-CCW)") (class "Default")
      (node (ref "R12") (pin "1") (pinfunction "CCW_1") (pintype "bidirectional"))
      (node (ref "R13") (pin "2") (pinfunction "2_2") (pintype "passive"))
    )
    (net (code "152") (name "Net-(R12-CW)") (class "Default")
      (node (ref "R11") (pin "1") (pinfunction "1_1") (pintype "passive"))
      (node (ref "R12") (pin "3") (pinfunction "CW_3") (pintype "bidirectional"))
    )
    (net (code "153") (name "Net-(U1-PB6(XTAL1{slash}TOSC1))") (class "Default")
      (node (ref "C2") (pin "1") (pinfunction "1_1") (pintype "passive"))
      (node (ref "Q1") (pin "2") (pinfunction "2_2") (pintype "passive"))
      (node (ref "R2") (pin "2") (pinfunction "2_2") (pintype "passive"))
      (node (ref "U1") (pin "9") (pinfunction "PB6(XTAL1/TOSC1)_9") (pintype "bidirectional"))
    )
    (net (code "154") (name "Net-(U1-PB7(XTAL2{slash}TOSC2))") (class "Default")
      (node (ref "C3") (pin "1") (pinfunction "1_1") (pintype "passive"))
      (node (ref "Q1") (pin "1") (pinfunction "1_1") (pintype "passive"))
      (node (ref "R2") (pin "1") (pinfunction "1_1") (pintype "passive"))
      (node (ref "U1") (pin "10") (pinfunction "PB7(XTAL2/TOSC2)_10") (pintype "bidirectional"))
    )
    (net (code "155") (name "SCK") (class "Default")
      (node (ref "JP2") (pin "4") (pinfunction "4_4") (pintype "passive"))
      (node (ref "U1") (pin "19") (pinfunction "PB5(SCK)_19") (pintype "bidirectional"))
    )
    (net (code "156") (name "unconnected-(IC7E-I-Pad11)") (class "Default")
      (node (ref "IC7") (pin "11") (pinfunction "I_11") (pintype "input"))
    )
    (net (code "157") (name "unconnected-(IC7E-O-Pad12)") (class "Default")
      (node (ref "IC7") (pin "12") (pinfunction "O_12") (pintype "output"))
    )
    (net (code "158") (name "unconnected-(IC7F-I-Pad14)") (class "Default")
      (node (ref "IC7") (pin "14") (pinfunction "I_14") (pintype "input"))
    )
    (net (code "159") (name "unconnected-(IC7F-O-Pad15)") (class "Default")
      (node (ref "IC7") (pin "15") (pinfunction "O_15") (pintype "output"))
    )
    (net (code "160") (name "unconnected-(IC8E-I-Pad11)") (class "Default")
      (node (ref "IC8") (pin "11") (pinfunction "I_11") (pintype "input"))
    )
    (net (code "161") (name "unconnected-(IC8E-O-Pad12)") (class "Default")
      (node (ref "IC8") (pin "12") (pinfunction "O_12") (pintype "output"))
    )
    (net (code "162") (name "unconnected-(IC8F-I-Pad14)") (class "Default")
      (node (ref "IC8") (pin "14") (pinfunction "I_14") (pintype "input"))
    )
    (net (code "163") (name "unconnected-(IC8F-O-Pad15)") (class "Default")
      (node (ref "IC8") (pin "15") (pinfunction "O_15") (pintype "output"))
    )
    (net (code "164") (name "unconnected-(J2-3-Pad2)") (class "Default")
      (node (ref "J2") (pin "2") (pinfunction "3_2") (pintype "passive"))
    )
    (net (code "165") (name "unconnected-(J3-3-Pad2)") (class "Default")
      (node (ref "J3") (pin "2") (pinfunction "3_2") (pintype "passive"))
    )
    (net (code "166") (name "unconnected-(J4-3-Pad2)") (class "Default")
      (node (ref "J4") (pin "2") (pinfunction "3_2") (pintype "passive"))
    )
    (net (code "167") (name "unconnected-(J5-3-Pad2)") (class "Default")
      (node (ref "J5") (pin "2") (pinfunction "3_2") (pintype "passive"))
    )
    (net (code "168") (name "unconnected-(J6-3-Pad2)") (class "Default")
      (node (ref "J6") (pin "2") (pinfunction "3_2") (pintype "passive"))
    )
    (net (code "169") (name "unconnected-(J7-3-Pad2)") (class "Default")
      (node (ref "J7") (pin "2") (pinfunction "3_2") (pintype "passive"))
    )
    (net (code "170") (name "unconnected-(J8-3-Pad2)") (class "Default")
      (node (ref "J8") (pin "2") (pinfunction "3_2") (pintype "passive"))
    )
    (net (code "171") (name "unconnected-(J9-3-Pad2)") (class "Default")
      (node (ref "J9") (pin "2") (pinfunction "3_2") (pintype "passive"))
    )
    (net (code "172") (name "unconnected-(J10-3-Pad2)") (class "Default")
      (node (ref "J10") (pin "2") (pinfunction "3_2") (pintype "passive"))
    )
    (net (code "173") (name "unconnected-(J11-3-Pad2)") (class "Default")
      (node (ref "J11") (pin "2") (pinfunction "3_2") (pintype "passive"))
    )
    (net (code "174") (name "unconnected-(J12-3-Pad2)") (class "Default")
      (node (ref "J12") (pin "2") (pinfunction "3_2") (pintype "passive"))
    )
    (net (code "175") (name "unconnected-(J13-3-Pad2)") (class "Default")
      (node (ref "J13") (pin "2") (pinfunction "3_2") (pintype "passive"))
    )
    (net (code "176") (name "unconnected-(J14-3-Pad2)") (class "Default")
      (node (ref "J14") (pin "2") (pinfunction "3_2") (pintype "passive"))
    )
    (net (code "177") (name "unconnected-(J15-3-Pad2)") (class "Default")
      (node (ref "J15") (pin "2") (pinfunction "3_2") (pintype "passive"))
    )
    (net (code "178") (name "unconnected-(J16-3-Pad2)") (class "Default")
      (node (ref "J16") (pin "2") (pinfunction "3_2") (pintype "passive"))
    )
    (net (code "179") (name "unconnected-(J17-3-Pad2)") (class "Default")
      (node (ref "J17") (pin "2") (pinfunction "3_2") (pintype "passive"))
    )
    (net (code "180") (name "unconnected-(J18-3-Pad2)") (class "Default")
      (node (ref "J18") (pin "2") (pinfunction "3_2") (pintype "passive"))
    )
    (net (code "181") (name "unconnected-(J19-3-Pad2)") (class "Default")
      (node (ref "J19") (pin "2") (pinfunction "3_2") (pintype "passive"))
    )
    (net (code "182") (name "unconnected-(OK1-VB-Pad7)") (class "Default")
      (node (ref "OK1") (pin "7") (pinfunction "VB_7") (pintype "passive"))
    )
    (net (code "183") (name "unconnected-(U1-AREF-Pad21)") (class "Default")
      (node (ref "U1") (pin "21") (pinfunction "AREF_21") (pintype "bidirectional"))
    )
    (net (code "184") (name "unconnected-(U1-PD1(TXD)-Pad3)") (class "Default")
      (node (ref "U1") (pin "3") (pinfunction "PD1(TXD)_3") (pintype "bidirectional"))
    )
  )
)
